# SCH_23GXSTM32F103Ext_2023-10-17.net
KiCad netlist of a schematic drawn in EasyEDA
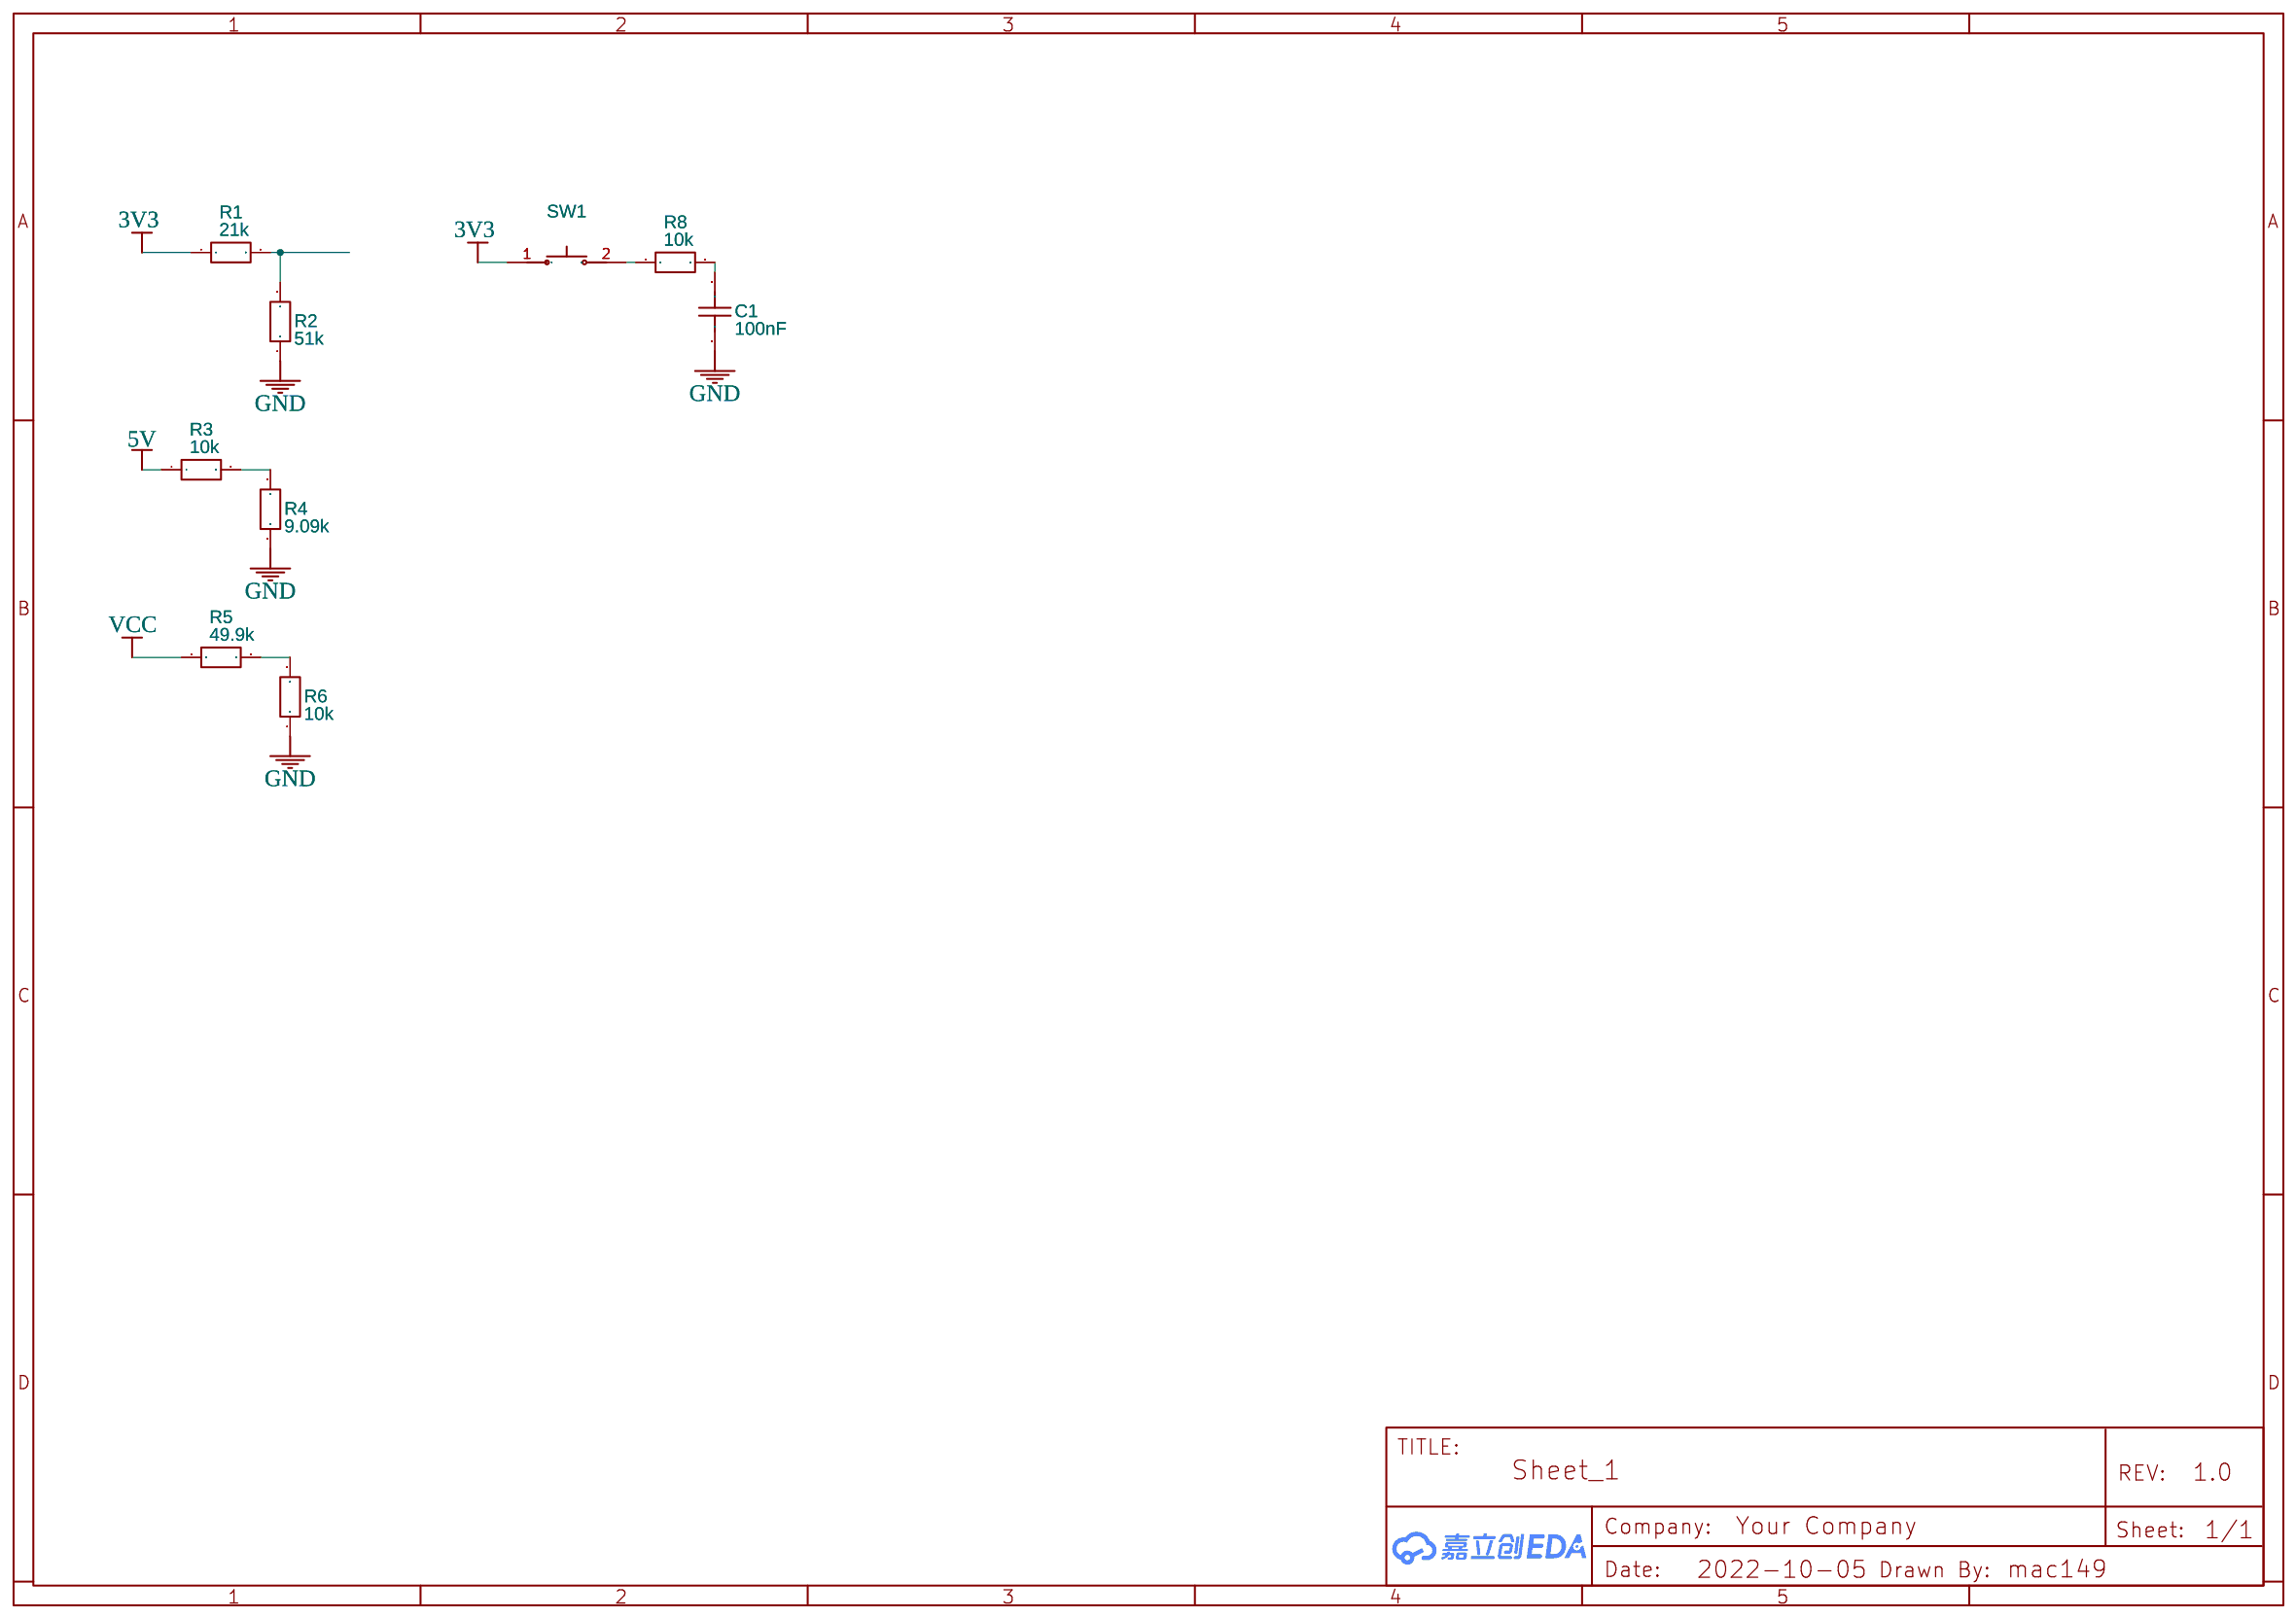
[diagram p0: Sheet_1]
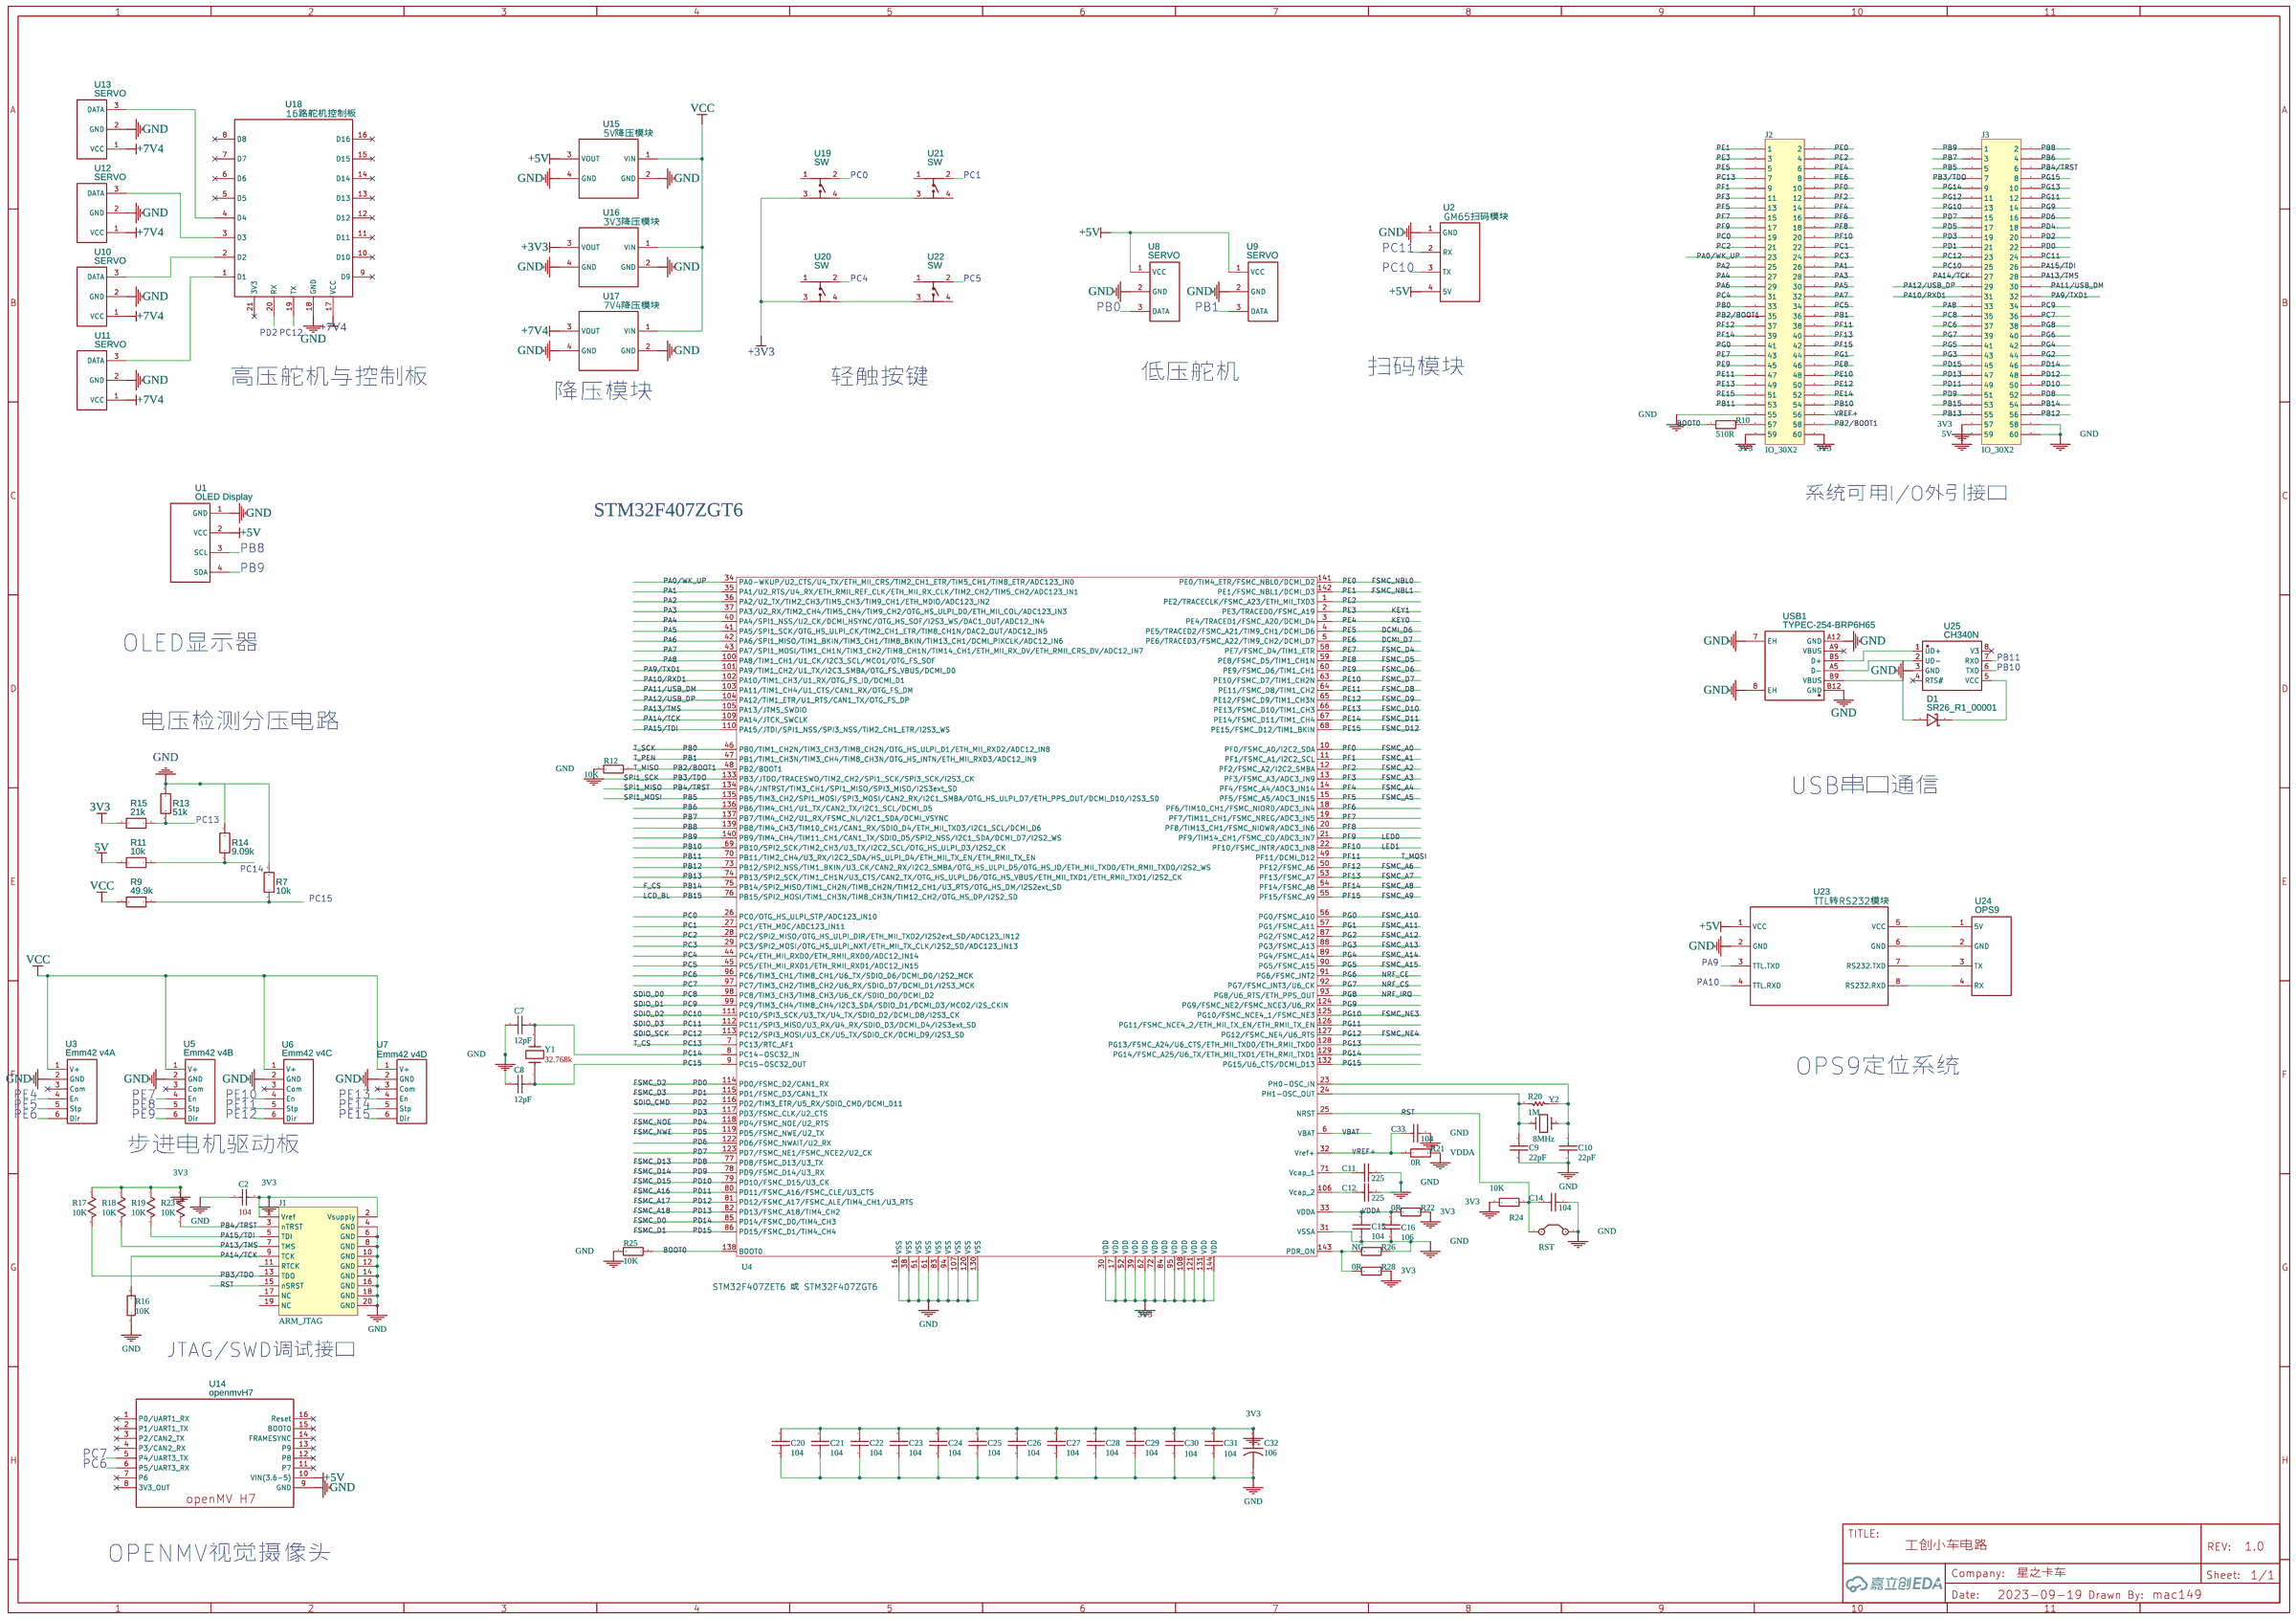
[diagram p1: Copy of STM32_F407.SchDoc]

(export (version "E")
  (design (tool "Eeschema 10.0.6"))
  (components
    (comp (ref "C1") (value "100nF") (libsource (lib "") (part "C_0603_US")))
    (comp (ref "R1") (value "21k") (libsource (lib "") (part "R_0603_EU_1")))
    (comp (ref "R2") (value "51k") (libsource (lib "") (part "R_0805_EU")))
    (comp (ref "R3") (value "10k") (libsource (lib "") (part "R_0805_EU_1")))
    (comp (ref "R4") (value "9.09k") (libsource (lib "") (part "R_0603_EU")))
    (comp (ref "R5") (value "49.9k") (libsource (lib "") (part "R_0805_EU_1")))
    (comp (ref "R6") (value "10k") (libsource (lib "") (part "R_0805_EU")))
    (comp (ref "R8") (value "10k") (libsource (lib "") (part "R_0603_EU_1")))
    (comp (ref "SW1")
      (value "TS3625A")
      (fields (field (name "Manufacturer") "SHOU HAN(首韩)"))
      (libsource (lib "") (part "TS3625A"))
    )
    (comp (ref "C2") (value "NO") (libsource (lib "") (part "Unknown_240_-435")))
    (comp (ref "C7") (value "12pF") (libsource (lib "") (part "Unknown_525_-600")))
    (comp (ref "C8") (value "12pF") (libsource (lib "") (part "Unknown_525_-540")))
    (comp (ref "C9") (value "22pF") (libsource (lib "") (part "Unknown_1540_-475")))
    (comp (ref "C10") (value "22pF") (libsource (lib "") (part "Unknown_1590_-475")))
    (comp (ref "C11") (value "225") (libsource (lib "") (part "Unknown_1385_-450")))
    (comp (ref "C12") (value "225") (libsource (lib "") (part "Unknown_1385_-430")))
    (comp (ref "C14") (value "104") (libsource (lib "") (part "Unknown_1575_-420")))
    (comp (ref "C15") (value "104") (libsource (lib "") (part "Unknown_1380_-395")))
    (comp (ref "C16") (value "106") (libsource (lib "") (part "Unknown_1410_-395")))
    (comp (ref "C20") (value "104") (libsource (lib "") (part "Unknown_790_-175")))
    (comp (ref "C21") (value "104") (libsource (lib "") (part "Unknown_830_-175")))
    (comp (ref "C22") (value "104") (libsource (lib "") (part "Unknown_870_-175")))
    (comp (ref "C23") (value "104") (libsource (lib "") (part "Unknown_910_-175")))
    (comp (ref "C24") (value "104") (libsource (lib "") (part "Unknown_950_-175")))
    (comp (ref "C25") (value "104") (libsource (lib "") (part "Unknown_990_-175")))
    (comp (ref "C26") (value "104") (libsource (lib "") (part "Unknown_1030_-175")))
    (comp (ref "C27") (value "104") (libsource (lib "") (part "Unknown_1070_-175")))
    (comp (ref "C28") (value "104") (libsource (lib "") (part "Unknown_1110_-175")))
    (comp (ref "C29") (value "104") (libsource (lib "") (part "Unknown_1150_-175")))
    (comp (ref "C30") (value "104") (libsource (lib "") (part "Unknown_1190_-175")))
    (comp (ref "C31") (value "104") (libsource (lib "") (part "Unknown_1230_-175")))
    (comp (ref "C32") (value "106") (libsource (lib "") (part "Unknown_1260_-180")))
    (comp (ref "C33") (value "104") (libsource (lib "") (part "Unknown_1435_-490")))
    (comp (ref "D1")
      (value "SR26_R1_00001")
      (fields (field (name "Manufacturer") "PANJIT(强茂)"))
      (libsource (lib "") (part "SR26_R1_00001"))
    )
    (comp (ref "J1") (value "ARM_JTAG") (libsource (lib "") (part "Unknown_280_-415")))
    (comp (ref "J2") (value "IO_30X2") (libsource (lib "") (part "Unknown_1790_-1500")))
    (comp (ref "J3") (value "IO_30X2") (libsource (lib "") (part "Unknown_2010_-1500")))
    (comp (ref "R7") (value "10k") (libsource (lib "") (part "R_0805_EU_1")))
    (comp (ref "R9") (value "49.9k") (libsource (lib "") (part "R_0805_EU")))
    (comp (ref "R10") (value "510R") (libsource (lib "") (part "Unknown_1760_-1200")))
    (comp (ref "R11") (value "10k") (libsource (lib "") (part "R_0805_EU")))
    (comp (ref "R12") (value "10K") (libsource (lib "") (part "Unknown_630_-850")))
    (comp (ref "R13") (value "51k") (libsource (lib "") (part "R_0805_EU_1")))
    (comp (ref "R14") (value "9.09k") (libsource (lib "") (part "R_0603_EU_1")))
    (comp (ref "R15") (value "21k") (libsource (lib "") (part "R_0603_EU")))
    (comp (ref "R16") (value "10K") (libsource (lib "") (part "Unknown_120_-305")))
    (comp (ref "R17") (value "10K") (libsource (lib "") (part "Unknown_90_-415")))
    (comp (ref "R18") (value "10K") (libsource (lib "") (part "Unknown_120_-415")))
    (comp (ref "R19") (value "10K") (libsource (lib "") (part "Unknown_150_-415")))
    (comp (ref "R20") (value "1M") (libsource (lib "") (part "Unknown_1570_-530")))
    (comp (ref "R21") (value "0R") (libsource (lib "") (part "Unknown_1430_-480")))
    (comp (ref "R22") (value "0R") (libsource (lib "") (part "Unknown_1420_-420")))
    (comp (ref "R23") (value "10K") (libsource (lib "") (part "Unknown_180_-415")))
    (comp (ref "R24") (value "10K") (libsource (lib "") (part "Unknown_1540_-410")))
    (comp (ref "R25") (value "10K") (libsource (lib "") (part "Unknown_650_-380")))
    (comp (ref "R26") (value "NC") (libsource (lib "") (part "Unknown_1380_-380")))
    (comp (ref "R28") (value "0R") (libsource (lib "") (part "Unknown_1380_-360")))
    (comp (ref "RST") (value "Key") (libsource (lib "") (part "Unknown_1560_-400")))
    (comp (ref "U1") (value "OLED Display") (libsource (lib "") (part "OLED Display")))
    (comp (ref "U2") (value "GM65扫码模块") (libsource (lib "") (part "GM65")))
    (comp (ref "U3") (value "Emm42 v4A") (libsource (lib "") (part "Emm42 v4")))
    (comp (ref "U4") (value "STM32F407ZET6 或 STM32F407ZGT6") (libsource (lib "") (part "Unknown_730_-1050")))
    (comp (ref "U5") (value "Emm42 v4B") (libsource (lib "") (part "Emm42 v4")))
    (comp (ref "U6") (value "Emm42 v4C") (libsource (lib "") (part "Emm42 v4")))
    (comp (ref "U7") (value "Emm42 v4D") (libsource (lib "") (part "Emm42 v4")))
    (comp (ref "U8") (value "SERVO") (libsource (lib "") (part "SERVO_1")))
    (comp (ref "U9") (value "SERVO") (libsource (lib "") (part "SERVO_1")))
    (comp (ref "U10") (value "SERVO") (libsource (lib "") (part "SERVO")))
    (comp (ref "U11") (value "SERVO") (libsource (lib "") (part "SERVO")))
    (comp (ref "U12") (value "SERVO") (libsource (lib "") (part "SERVO")))
    (comp (ref "U13") (value "SERVO") (libsource (lib "") (part "SERVO")))
    (comp (ref "U14") (value "openmvH7") (libsource (lib "") (part "openmvH7")))
    (comp (ref "U15") (value "5V降压模块") (libsource (lib "") (part "降压模块")))
    (comp (ref "U16") (value "3V3降压模块") (libsource (lib "") (part "降压模块")))
    (comp (ref "U17") (value "7V4降压模块") (libsource (lib "") (part "降压模块")))
    (comp (ref "U18") (value "16路舵机控制板") (libsource (lib "") (part "16路舵机控制板")))
    (comp (ref "U19")
      (value "SW")
      (fields
        (field (name "Manufacturer Part") "TD-1806SR-5.5H-250")
        (field (name "Manufacturer") "DEALON(德艺隆)")
      )
      (libsource (lib "") (part "TD-1806SR-5.5H-250"))
    )
    (comp (ref "U20")
      (value "SW")
      (fields
        (field (name "Manufacturer Part") "TD-1806SR-5.5H-250")
        (field (name "Manufacturer") "DEALON(德艺隆)")
      )
      (libsource (lib "") (part "TD-1806SR-5.5H-250"))
    )
    (comp (ref "U21")
      (value "SW")
      (fields
        (field (name "Manufacturer Part") "TD-1806SR-5.5H-250")
        (field (name "Manufacturer") "DEALON(德艺隆)")
      )
      (libsource (lib "") (part "TD-1806SR-5.5H-250"))
    )
    (comp (ref "U22")
      (value "SW")
      (fields
        (field (name "Manufacturer Part") "TD-1806SR-5.5H-250")
        (field (name "Manufacturer") "DEALON(德艺隆)")
      )
      (libsource (lib "") (part "TD-1806SR-5.5H-250"))
    )
    (comp (ref "U23") (value "TTL转RS232模块") (libsource (lib "") (part "TTL转RS232模块")))
    (comp (ref "U24") (value "OPS9") (libsource (lib "") (part "GM65_1")))
    (comp (ref "U25")
      (value "CH340N")
      (fields (field (name "Manufacturer") "WCH(南京沁恒)"))
      (libsource (lib "") (part "CH340N"))
    )
    (comp (ref "USB1")
      (value "TYPEC-254-BRP6H65")
      (fields (field (name "Manufacturer") "XUNPU(讯普)"))
      (libsource (lib "") (part "TYPEC-254-BRP6H65"))
    )
    (comp (ref "Y1") (value "8MHz") (libsource (lib "") (part "Unknown_550_-560")))
    (comp (ref "Y2") (value "8MHz") (libsource (lib "") (part "Unknown_1565_-500")))
  )
  (nets
    (net (code "1") (name "+3V3") (class "Default")
      (node (ref "U16") (pin "3") (pinfunction "VOUT_3") (pintype "unspecified"))
      (node (ref "U19") (pin "3") (pinfunction "C_3") (pintype "unspecified"))
      (node (ref "U20") (pin "3") (pinfunction "C_3") (pintype "unspecified"))
    )
    (net (code "2") (name "+5V") (class "Default")
      (node (ref "U1") (pin "2") (pinfunction "VCC_2") (pintype "unspecified"))
      (node (ref "U14") (pin "10") (pinfunction "VIN(3.6-5)_10") (pintype "unspecified"))
      (node (ref "U15") (pin "3") (pinfunction "VOUT_3") (pintype "unspecified"))
      (node (ref "U2") (pin "4") (pinfunction "5V_4") (pintype "unspecified"))
      (node (ref "U23") (pin "1") (pinfunction "VCC_1") (pintype "unspecified"))
      (node (ref "U8") (pin "1") (pinfunction "VCC_1") (pintype "unspecified"))
      (node (ref "U9") (pin "1") (pinfunction "VCC_1") (pintype "unspecified"))
    )
    (net (code "3") (name "+7V4") (class "Default")
      (node (ref "U10") (pin "1") (pinfunction "VCC_1") (pintype "unspecified"))
      (node (ref "U11") (pin "1") (pinfunction "VCC_1") (pintype "unspecified"))
      (node (ref "U12") (pin "1") (pinfunction "VCC_1") (pintype "unspecified"))
      (node (ref "U13") (pin "1") (pinfunction "VCC_1") (pintype "unspecified"))
      (node (ref "U17") (pin "3") (pinfunction "VOUT_3") (pintype "unspecified"))
      (node (ref "U18") (pin "17") (pinfunction "VCC_17") (pintype "unspecified"))
    )
    (net (code "4") (name "3V3") (class "Default")
      (node (ref "C2") (pin "2") (pinfunction "2_2") (pintype "unspecified"))
      (node (ref "C20") (pin "1") (pinfunction "1_1") (pintype "unspecified"))
      (node (ref "C21") (pin "1") (pinfunction "1_1") (pintype "unspecified"))
      (node (ref "C22") (pin "1") (pinfunction "1_1") (pintype "unspecified"))
      (node (ref "C23") (pin "1") (pinfunction "1_1") (pintype "unspecified"))
      (node (ref "C24") (pin "1") (pinfunction "1_1") (pintype "unspecified"))
      (node (ref "C25") (pin "1") (pinfunction "1_1") (pintype "unspecified"))
      (node (ref "C26") (pin "1") (pinfunction "1_1") (pintype "unspecified"))
      (node (ref "C27") (pin "1") (pinfunction "1_1") (pintype "unspecified"))
      (node (ref "C28") (pin "1") (pinfunction "1_1") (pintype "unspecified"))
      (node (ref "C29") (pin "1") (pinfunction "1_1") (pintype "unspecified"))
      (node (ref "C30") (pin "1") (pinfunction "1_1") (pintype "unspecified"))
      (node (ref "C31") (pin "1") (pinfunction "1_1") (pintype "unspecified"))
      (node (ref "C32") (pin "1") (pinfunction "1_1") (pintype "unspecified"))
      (node (ref "J1") (pin "1") (pinfunction "Vref_1") (pintype "unspecified"))
      (node (ref "J1") (pin "2") (pinfunction "Vsupply_2") (pintype "unspecified"))
      (node (ref "J2") (pin "59") (pinfunction "59_59") (pintype "unspecified"))
      (node (ref "J2") (pin "60") (pinfunction "60_60") (pintype "unspecified"))
      (node (ref "J3") (pin "57") (pinfunction "57_57") (pintype "unspecified"))
      (node (ref "R1") (pin "1") (pinfunction "1_1") (pintype "unspecified"))
      (node (ref "R15") (pin "1") (pinfunction "1_1") (pintype "unspecified"))
      (node (ref "R17") (pin "1") (pinfunction "1_1") (pintype "unspecified"))
      (node (ref "R18") (pin "1") (pinfunction "1_1") (pintype "unspecified"))
      (node (ref "R19") (pin "1") (pinfunction "1_1") (pintype "unspecified"))
      (node (ref "R22") (pin "2") (pinfunction "2_2") (pintype "unspecified"))
      (node (ref "R23") (pin "1") (pinfunction "1_1") (pintype "unspecified"))
      (node (ref "R24") (pin "2") (pinfunction "2_2") (pintype "unspecified"))
      (node (ref "R28") (pin "2") (pinfunction "2_2") (pintype "unspecified"))
      (node (ref "SW1") (pin "1") (pinfunction "1_1") (pintype "unspecified"))
      (node (ref "U4") (pin "108") (pinfunction "VDD_108") (pintype "unspecified"))
      (node (ref "U4") (pin "121") (pinfunction "VDD_121") (pintype "unspecified"))
      (node (ref "U4") (pin "131") (pinfunction "VDD_131") (pintype "unspecified"))
      (node (ref "U4") (pin "144") (pinfunction "VDD_144") (pintype "unspecified"))
      (node (ref "U4") (pin "17") (pinfunction "VDD_17") (pintype "unspecified"))
      (node (ref "U4") (pin "30") (pinfunction "VDD_30") (pintype "unspecified"))
      (node (ref "U4") (pin "39") (pinfunction "VDD_39") (pintype "unspecified"))
      (node (ref "U4") (pin "52") (pinfunction "VDD_52") (pintype "unspecified"))
      (node (ref "U4") (pin "62") (pinfunction "VDD_62") (pintype "unspecified"))
      (node (ref "U4") (pin "72") (pinfunction "VDD_72") (pintype "unspecified"))
      (node (ref "U4") (pin "84") (pinfunction "VDD_84") (pintype "unspecified"))
      (node (ref "U4") (pin "95") (pinfunction "VDD_95") (pintype "unspecified"))
    )
    (net (code "5") (name "5V") (class "Default")
      (node (ref "J3") (pin "59") (pinfunction "59_59") (pintype "unspecified"))
      (node (ref "R11") (pin "1") (pinfunction "1_1") (pintype "unspecified"))
      (node (ref "R3") (pin "1") (pinfunction "1_1") (pintype "unspecified"))
    )
    (net (code "6") (name "BOOT0") (class "Default")
      (node (ref "R10") (pin "2") (pinfunction "2_2") (pintype "unspecified"))
      (node (ref "R25") (pin "1") (pinfunction "1_1") (pintype "unspecified"))
      (node (ref "U4") (pin "138") (pinfunction "BOOT0_138") (pintype "unspecified"))
    )
    (net (code "7") (name "DCMI_D6") (class "Default")
      (node (ref "J2") (pin "5") (pinfunction "5_5") (pintype "unspecified"))
      (node (ref "U4") (pin "4") (pinfunction "PE5/TRACED2/FSMC_A21/TIM9_CH1/DCMI_D6_4") (pintype "unspecified"))
    )
    (net (code "8") (name "DCMI_D7") (class "Default")
      (node (ref "J2") (pin "8") (pinfunction "8_8") (pintype "unspecified"))
      (node (ref "U4") (pin "5") (pinfunction "PE6/TRACED3/FSMC_A22/TIM9_CH2/DCMI_D7_5") (pintype "unspecified"))
    )
    (net (code "9") (name "FSMC_A0") (class "Default")
      (node (ref "J2") (pin "10") (pinfunction "10_10") (pintype "unspecified"))
      (node (ref "U4") (pin "10") (pinfunction "PF0/FSMC_A0/I2C2_SDA_10") (pintype "unspecified"))
    )
    (net (code "10") (name "FSMC_A1") (class "Default")
      (node (ref "J2") (pin "9") (pinfunction "9_9") (pintype "unspecified"))
      (node (ref "U4") (pin "11") (pinfunction "PF1/FSMC_A1/I2C2_SCL_11") (pintype "unspecified"))
    )
    (net (code "11") (name "FSMC_A2") (class "Default")
      (node (ref "J2") (pin "12") (pinfunction "12_12") (pintype "unspecified"))
      (node (ref "U4") (pin "12") (pinfunction "PF2/FSMC_A2/I2C2_SMBA_12") (pintype "unspecified"))
    )
    (net (code "12") (name "FSMC_A3") (class "Default")
      (node (ref "J2") (pin "11") (pinfunction "11_11") (pintype "unspecified"))
      (node (ref "U4") (pin "13") (pinfunction "PF3/FSMC_A3/ADC3_IN9_13") (pintype "unspecified"))
    )
    (net (code "13") (name "FSMC_A4") (class "Default")
      (node (ref "J2") (pin "14") (pinfunction "14_14") (pintype "unspecified"))
      (node (ref "U4") (pin "14") (pinfunction "PF4/FSMC_A4/ADC3_IN14_14") (pintype "unspecified"))
    )
    (net (code "14") (name "FSMC_A5") (class "Default")
      (node (ref "J2") (pin "13") (pinfunction "13_13") (pintype "unspecified"))
      (node (ref "U4") (pin "15") (pinfunction "PF5/FSMC_A5/ADC3_IN15_15") (pintype "unspecified"))
    )
    (net (code "15") (name "FSMC_A6") (class "Default")
      (node (ref "J2") (pin "37") (pinfunction "37_37") (pintype "unspecified"))
      (node (ref "U4") (pin "50") (pinfunction "PF12/FSMC_A6_50") (pintype "unspecified"))
    )
    (net (code "16") (name "FSMC_A7") (class "Default")
      (node (ref "J2") (pin "40") (pinfunction "40_40") (pintype "unspecified"))
      (node (ref "U4") (pin "53") (pinfunction "PF13/FSMC_A7_53") (pintype "unspecified"))
    )
    (net (code "17") (name "FSMC_A8") (class "Default")
      (node (ref "J2") (pin "39") (pinfunction "39_39") (pintype "unspecified"))
      (node (ref "U4") (pin "54") (pinfunction "PF14/FSMC_A8_54") (pintype "unspecified"))
    )
    (net (code "18") (name "FSMC_A9") (class "Default")
      (node (ref "J2") (pin "42") (pinfunction "42_42") (pintype "unspecified"))
      (node (ref "U4") (pin "55") (pinfunction "PF15/FSMC_A9_55") (pintype "unspecified"))
    )
    (net (code "19") (name "FSMC_A10") (class "Default")
      (node (ref "J2") (pin "41") (pinfunction "41_41") (pintype "unspecified"))
      (node (ref "U4") (pin "56") (pinfunction "PG0/FSMC_A10_56") (pintype "unspecified"))
    )
    (net (code "20") (name "FSMC_A11") (class "Default")
      (node (ref "J2") (pin "44") (pinfunction "44_44") (pintype "unspecified"))
      (node (ref "U4") (pin "57") (pinfunction "PG1/FSMC_A11_57") (pintype "unspecified"))
    )
    (net (code "21") (name "FSMC_A12") (class "Default")
      (node (ref "J3") (pin "44") (pinfunction "44_44") (pintype "unspecified"))
      (node (ref "U4") (pin "87") (pinfunction "PG2/FSMC_A12_87") (pintype "unspecified"))
    )
    (net (code "22") (name "FSMC_A13") (class "Default")
      (node (ref "J3") (pin "43") (pinfunction "43_43") (pintype "unspecified"))
      (node (ref "U4") (pin "88") (pinfunction "PG3/FSMC_A13_88") (pintype "unspecified"))
    )
    (net (code "23") (name "FSMC_A14") (class "Default")
      (node (ref "J3") (pin "42") (pinfunction "42_42") (pintype "unspecified"))
      (node (ref "U4") (pin "89") (pinfunction "PG4/FSMC_A14_89") (pintype "unspecified"))
    )
    (net (code "24") (name "FSMC_A15") (class "Default")
      (node (ref "J3") (pin "41") (pinfunction "41_41") (pintype "unspecified"))
      (node (ref "U4") (pin "90") (pinfunction "PG5/FSMC_A15_90") (pintype "unspecified"))
    )
    (net (code "25") (name "FSMC_A16") (class "Default")
      (node (ref "J3") (pin "49") (pinfunction "49_49") (pintype "unspecified"))
      (node (ref "U4") (pin "80") (pinfunction "PD11/FSMC_A16/FSMC_CLE/U3_CTS_80") (pintype "unspecified"))
    )
    (net (code "26") (name "FSMC_A17") (class "Default")
      (node (ref "J3") (pin "48") (pinfunction "48_48") (pintype "unspecified"))
      (node (ref "U4") (pin "81") (pinfunction "PD12/FSMC_A17/FSMC_ALE/TIM4_CH1/U3_RTS_81") (pintype "unspecified"))
    )
    (net (code "27") (name "FSMC_A18") (class "Default")
      (node (ref "J3") (pin "47") (pinfunction "47_47") (pintype "unspecified"))
      (node (ref "U4") (pin "82") (pinfunction "PD13/FSMC_A18/TIM4_CH2_82") (pintype "unspecified"))
    )
    (net (code "28") (name "FSMC_D0") (class "Default")
      (node (ref "J3") (pin "46") (pinfunction "46_46") (pintype "unspecified"))
      (node (ref "U4") (pin "85") (pinfunction "PD14/FSMC_D0/TIM4_CH3_85") (pintype "unspecified"))
    )
    (net (code "29") (name "FSMC_D1") (class "Default")
      (node (ref "J3") (pin "45") (pinfunction "45_45") (pintype "unspecified"))
      (node (ref "U4") (pin "86") (pinfunction "PD15/FSMC_D1/TIM4_CH4_86") (pintype "unspecified"))
    )
    (net (code "30") (name "FSMC_D2") (class "Default")
      (node (ref "J3") (pin "22") (pinfunction "22_22") (pintype "unspecified"))
      (node (ref "U4") (pin "114") (pinfunction "PD0/FSMC_D2/CAN1_RX_114") (pintype "unspecified"))
    )
    (net (code "31") (name "FSMC_D3") (class "Default")
      (node (ref "J3") (pin "21") (pinfunction "21_21") (pintype "unspecified"))
      (node (ref "U4") (pin "115") (pinfunction "PD1/FSMC_D3/CAN1_TX_115") (pintype "unspecified"))
    )
    (net (code "32") (name "FSMC_D4") (class "Default")
      (node (ref "J2") (pin "43") (pinfunction "43_43") (pintype "unspecified"))
      (node (ref "U4") (pin "58") (pinfunction "PE7/FSMC_D4/TIM1_ETR_58") (pintype "unspecified"))
    )
    (net (code "33") (name "FSMC_D5") (class "Default")
      (node (ref "J2") (pin "46") (pinfunction "46_46") (pintype "unspecified"))
      (node (ref "U4") (pin "59") (pinfunction "PE8/FSMC_D5/TIM1_CH1N_59") (pintype "unspecified"))
    )
    (net (code "34") (name "FSMC_D6") (class "Default")
      (node (ref "J2") (pin "45") (pinfunction "45_45") (pintype "unspecified"))
      (node (ref "U4") (pin "60") (pinfunction "PE9/FSMC_D6/TIM1_CH1_60") (pintype "unspecified"))
    )
    (net (code "35") (name "FSMC_D7") (class "Default")
      (node (ref "J2") (pin "48") (pinfunction "48_48") (pintype "unspecified"))
      (node (ref "U4") (pin "63") (pinfunction "PE10/FSMC_D7/TIM1_CH2N_63") (pintype "unspecified"))
    )
    (net (code "36") (name "FSMC_D8") (class "Default")
      (node (ref "J2") (pin "47") (pinfunction "47_47") (pintype "unspecified"))
      (node (ref "U4") (pin "64") (pinfunction "PE11/FSMC_D8/TIM1_CH2_64") (pintype "unspecified"))
    )
    (net (code "37") (name "FSMC_D9") (class "Default")
      (node (ref "J2") (pin "50") (pinfunction "50_50") (pintype "unspecified"))
      (node (ref "U4") (pin "65") (pinfunction "PE12/FSMC_D9/TIM1_CH3N_65") (pintype "unspecified"))
    )
    (net (code "38") (name "FSMC_D10") (class "Default")
      (node (ref "J2") (pin "49") (pinfunction "49_49") (pintype "unspecified"))
      (node (ref "U4") (pin "66") (pinfunction "PE13/FSMC_D10/TIM1_CH3_66") (pintype "unspecified"))
    )
    (net (code "39") (name "FSMC_D11") (class "Default")
      (node (ref "J2") (pin "52") (pinfunction "52_52") (pintype "unspecified"))
      (node (ref "U4") (pin "67") (pinfunction "PE14/FSMC_D11/TIM1_CH4_67") (pintype "unspecified"))
    )
    (net (code "40") (name "FSMC_D12") (class "Default")
      (node (ref "J2") (pin "51") (pinfunction "51_51") (pintype "unspecified"))
      (node (ref "U4") (pin "68") (pinfunction "PE15/FSMC_D12/TIM1_BKIN_68") (pintype "unspecified"))
    )
    (net (code "41") (name "FSMC_D13") (class "Default")
      (node (ref "J3") (pin "52") (pinfunction "52_52") (pintype "unspecified"))
      (node (ref "U4") (pin "77") (pinfunction "PD8/FSMC_D13/U3_TX_77") (pintype "unspecified"))
    )
    (net (code "42") (name "FSMC_D14") (class "Default")
      (node (ref "J3") (pin "51") (pinfunction "51_51") (pintype "unspecified"))
      (node (ref "U4") (pin "78") (pinfunction "PD9/FSMC_D14/U3_RX_78") (pintype "unspecified"))
    )
    (net (code "43") (name "FSMC_D15") (class "Default")
      (node (ref "J3") (pin "50") (pinfunction "50_50") (pintype "unspecified"))
      (node (ref "U4") (pin "79") (pinfunction "PD10/FSMC_D15/U3_CK_79") (pintype "unspecified"))
    )
    (net (code "44") (name "FSMC_NBL0") (class "Default")
      (node (ref "J2") (pin "2") (pinfunction "2_2") (pintype "unspecified"))
      (node (ref "U4") (pin "141") (pinfunction "PE0/TIM4_ETR/FSMC_NBL0/DCMI_D2_141") (pintype "unspecified"))
    )
    (net (code "45") (name "FSMC_NBL1") (class "Default")
      (node (ref "J2") (pin "1") (pinfunction "1_1") (pintype "unspecified"))
      (node (ref "U4") (pin "142") (pinfunction "PE1/FSMC_NBL1/DCMI_D3_142") (pintype "unspecified"))
    )
    (net (code "46") (name "FSMC_NE3") (class "Default")
      (node (ref "J3") (pin "13") (pinfunction "13_13") (pintype "unspecified"))
      (node (ref "U4") (pin "125") (pinfunction "PG10/FSMC_NCE4_1/FSMC_NE3_125") (pintype "unspecified"))
    )
    (net (code "47") (name "FSMC_NE4") (class "Default")
      (node (ref "J3") (pin "11") (pinfunction "11_11") (pintype "unspecified"))
      (node (ref "U4") (pin "127") (pinfunction "PG12/FSMC_NE4/U6_RTS_127") (pintype "unspecified"))
    )
    (net (code "48") (name "FSMC_NOE") (class "Default")
      (node (ref "J3") (pin "18") (pinfunction "18_18") (pintype "unspecified"))
      (node (ref "U4") (pin "118") (pinfunction "PD4/FSMC_NOE/U2_RTS_118") (pintype "unspecified"))
    )
    (net (code "49") (name "FSMC_NWE") (class "Default")
      (node (ref "J3") (pin "17") (pinfunction "17_17") (pintype "unspecified"))
      (node (ref "U4") (pin "119") (pinfunction "PD5/FSMC_NWE/U2_TX_119") (pintype "unspecified"))
    )
    (net (code "50") (name "F_CS") (class "Default")
      (node (ref "J3") (pin "54") (pinfunction "54_54") (pintype "unspecified"))
      (node (ref "U4") (pin "75") (pinfunction "PB14/SPI2_MISO/TIM1_CH2N/TIM8_CH2N/TIM12_CH1/U3_RTS/OTG_HS_DM/I2S2ext_SD_75") (pintype "unspecified"))
    )
    (net (code "51") (name "GND") (class "Default")
      (node (ref "C1") (pin "1") (pinfunction "1_1") (pintype "unspecified"))
      (node (ref "C10") (pin "2") (pinfunction "2_2") (pintype "unspecified"))
      (node (ref "C11") (pin "2") (pinfunction "2_2") (pintype "unspecified"))
      (node (ref "C12") (pin "2") (pinfunction "2_2") (pintype "unspecified"))
      (node (ref "C14") (pin "1") (pinfunction "1_1") (pintype "unspecified"))
      (node (ref "C15") (pin "1") (pinfunction "1_1") (pintype "unspecified"))
      (node (ref "C16") (pin "1") (pinfunction "1_1") (pintype "unspecified"))
      (node (ref "C2") (pin "1") (pinfunction "1_1") (pintype "unspecified"))
      (node (ref "C20") (pin "2") (pinfunction "2_2") (pintype "unspecified"))
      (node (ref "C21") (pin "2") (pinfunction "2_2") (pintype "unspecified"))
      (node (ref "C22") (pin "2") (pinfunction "2_2") (pintype "unspecified"))
      (node (ref "C23") (pin "2") (pinfunction "2_2") (pintype "unspecified"))
      (node (ref "C24") (pin "2") (pinfunction "2_2") (pintype "unspecified"))
      (node (ref "C25") (pin "2") (pinfunction "2_2") (pintype "unspecified"))
      (node (ref "C26") (pin "2") (pinfunction "2_2") (pintype "unspecified"))
      (node (ref "C27") (pin "2") (pinfunction "2_2") (pintype "unspecified"))
      (node (ref "C28") (pin "2") (pinfunction "2_2") (pintype "unspecified"))
      (node (ref "C29") (pin "2") (pinfunction "2_2") (pintype "unspecified"))
      (node (ref "C30") (pin "2") (pinfunction "2_2") (pintype "unspecified"))
      (node (ref "C31") (pin "2") (pinfunction "2_2") (pintype "unspecified"))
      (node (ref "C32") (pin "2") (pinfunction "2_2") (pintype "unspecified"))
      (node (ref "C33") (pin "2") (pinfunction "2_2") (pintype "unspecified"))
      (node (ref "C7") (pin "1") (pinfunction "1_1") (pintype "unspecified"))
      (node (ref "C8") (pin "1") (pinfunction "1_1") (pintype "unspecified"))
      (node (ref "C9") (pin "2") (pinfunction "2_2") (pintype "unspecified"))
      (node (ref "J1") (pin "10") (pinfunction "GND_10") (pintype "unspecified"))
      (node (ref "J1") (pin "12") (pinfunction "GND_12") (pintype "unspecified"))
      (node (ref "J1") (pin "14") (pinfunction "GND_14") (pintype "unspecified"))
      (node (ref "J1") (pin "16") (pinfunction "GND_16") (pintype "unspecified"))
      (node (ref "J1") (pin "18") (pinfunction "GND_18") (pintype "unspecified"))
      (node (ref "J1") (pin "20") (pinfunction "GND_20") (pintype "unspecified"))
      (node (ref "J1") (pin "4") (pinfunction "GND_4") (pintype "unspecified"))
      (node (ref "J1") (pin "6") (pinfunction "GND_6") (pintype "unspecified"))
      (node (ref "J1") (pin "8") (pinfunction "GND_8") (pintype "unspecified"))
      (node (ref "J2") (pin "55") (pinfunction "55_55") (pintype "unspecified"))
      (node (ref "J3") (pin "58") (pinfunction "58_58") (pintype "unspecified"))
      (node (ref "J3") (pin "60") (pinfunction "60_60") (pintype "unspecified"))
      (node (ref "R12") (pin "2") (pinfunction "2_2") (pintype "unspecified"))
      (node (ref "R13") (pin "2") (pinfunction "2_2") (pintype "unspecified"))
      (node (ref "R14") (pin "2") (pinfunction "2_2") (pintype "unspecified"))
      (node (ref "R16") (pin "1") (pinfunction "1_1") (pintype "unspecified"))
      (node (ref "R2") (pin "1") (pinfunction "1_1") (pintype "unspecified"))
      (node (ref "R25") (pin "2") (pinfunction "2_2") (pintype "unspecified"))
      (node (ref "R26") (pin "2") (pinfunction "2_2") (pintype "unspecified"))
      (node (ref "R4") (pin "1") (pinfunction "1_1") (pintype "unspecified"))
      (node (ref "R6") (pin "1") (pinfunction "1_1") (pintype "unspecified"))
      (node (ref "R7") (pin "2") (pinfunction "2_2") (pintype "unspecified"))
      (node (ref "RST") (pin "2") (pinfunction "C2_2") (pintype "unspecified"))
      (node (ref "U1") (pin "1") (pinfunction "GND_1") (pintype "unspecified"))
      (node (ref "U10") (pin "2") (pinfunction "GND_2") (pintype "unspecified"))
      (node (ref "U11") (pin "2") (pinfunction "GND_2") (pintype "unspecified"))
      (node (ref "U12") (pin "2") (pinfunction "GND_2") (pintype "unspecified"))
      (node (ref "U13") (pin "2") (pinfunction "GND_2") (pintype "unspecified"))
      (node (ref "U14") (pin "9") (pinfunction "GND_9") (pintype "unspecified"))
      (node (ref "U15") (pin "2") (pinfunction "GND_2") (pintype "unspecified"))
      (node (ref "U15") (pin "4") (pinfunction "GND_4") (pintype "unspecified"))
      (node (ref "U16") (pin "2") (pinfunction "GND_2") (pintype "unspecified"))
      (node (ref "U16") (pin "4") (pinfunction "GND_4") (pintype "unspecified"))
      (node (ref "U17") (pin "2") (pinfunction "GND_2") (pintype "unspecified"))
      (node (ref "U17") (pin "4") (pinfunction "GND_4") (pintype "unspecified"))
      (node (ref "U18") (pin "18") (pinfunction "GND_18") (pintype "unspecified"))
      (node (ref "U2") (pin "1") (pinfunction "GND_1") (pintype "unspecified"))
      (node (ref "U23") (pin "2") (pinfunction "GND_2") (pintype "unspecified"))
      (node (ref "U25") (pin "3") (pinfunction "GND_3") (pintype "unspecified"))
      (node (ref "U3") (pin "2") (pinfunction "GND_2") (pintype "unspecified"))
      (node (ref "U4") (pin "107") (pinfunction "VSS_107") (pintype "unspecified"))
      (node (ref "U4") (pin "120") (pinfunction "VSS_120") (pintype "unspecified"))
      (node (ref "U4") (pin "130") (pinfunction "VSS_130") (pintype "unspecified"))
      (node (ref "U4") (pin "16") (pinfunction "VSS_16") (pintype "unspecified"))
      (node (ref "U4") (pin "31") (pinfunction "VSSA_31") (pintype "unspecified"))
      (node (ref "U4") (pin "38") (pinfunction "VSS_38") (pintype "unspecified"))
      (node (ref "U4") (pin "51") (pinfunction "VSS_51") (pintype "unspecified"))
      (node (ref "U4") (pin "61") (pinfunction "VSS_61") (pintype "unspecified"))
      (node (ref "U4") (pin "83") (pinfunction "VSS_83") (pintype "unspecified"))
      (node (ref "U4") (pin "94") (pinfunction "VSS_94") (pintype "unspecified"))
      (node (ref "U5") (pin "2") (pinfunction "GND_2") (pintype "unspecified"))
      (node (ref "U6") (pin "2") (pinfunction "GND_2") (pintype "unspecified"))
      (node (ref "U7") (pin "2") (pinfunction "GND_2") (pintype "unspecified"))
      (node (ref "U8") (pin "2") (pinfunction "GND_2") (pintype "unspecified"))
      (node (ref "U9") (pin "2") (pinfunction "GND_2") (pintype "unspecified"))
      (node (ref "USB1") (pin "7") (pinfunction "EH_7") (pintype "unspecified"))
      (node (ref "USB1") (pin "8") (pinfunction "EH_8") (pintype "unspecified"))
      (node (ref "USB1") (pin "A12") (pinfunction "GND_A12") (pintype "unspecified"))
      (node (ref "USB1") (pin "B12") (pinfunction "GND_B12") (pintype "unspecified"))
    )
    (net (code "52") (name "KEY0") (class "Default")
      (node (ref "J2") (pin "6") (pinfunction "6_6") (pintype "unspecified"))
      (node (ref "U4") (pin "3") (pinfunction "PE4/TRACED1/FSMC_A20/DCMI_D4_3") (pintype "unspecified"))
    )
    (net (code "53") (name "KEY1") (class "Default")
      (node (ref "J2") (pin "3") (pinfunction "3_3") (pintype "unspecified"))
      (node (ref "U4") (pin "2") (pinfunction "PE3/TRACED0/FSMC_A19_2") (pintype "unspecified"))
    )
    (net (code "54") (name "LCD_BL") (class "Default")
      (node (ref "J3") (pin "53") (pinfunction "53_53") (pintype "unspecified"))
      (node (ref "U4") (pin "76") (pinfunction "PB15/SPI2_MOSI/TIM1_CH3N/TIM8_CH3N/TIM12_CH2/OTG_HS_DP/I2S2_SD_76") (pintype "unspecified"))
    )
    (net (code "55") (name "LED0") (class "Default")
      (node (ref "J2") (pin "17") (pinfunction "17_17") (pintype "unspecified"))
      (node (ref "U4") (pin "21") (pinfunction "PF9/TIM14_CH1/FSMC_CD/ADC3_IN7_21") (pintype "unspecified"))
    )
    (net (code "56") (name "LED1") (class "Default")
      (node (ref "J2") (pin "20") (pinfunction "20_20") (pintype "unspecified"))
      (node (ref "U4") (pin "22") (pinfunction "PF10/FSMC_INTR/ADC3_IN8_22") (pintype "unspecified"))
    )
    (net (code "57") (name "NRF_CE") (class "Default")
      (node (ref "J3") (pin "40") (pinfunction "40_40") (pintype "unspecified"))
      (node (ref "U4") (pin "91") (pinfunction "PG6/FSMC_INT2_91") (pintype "unspecified"))
    )
    (net (code "58") (name "NRF_CS") (class "Default")
      (node (ref "J3") (pin "39") (pinfunction "39_39") (pintype "unspecified"))
      (node (ref "U4") (pin "92") (pinfunction "PG7/FSMC_INT3/U6_CK_92") (pintype "unspecified"))
    )
    (net (code "59") (name "NRF_IRQ") (class "Default")
      (node (ref "J3") (pin "38") (pinfunction "38_38") (pintype "unspecified"))
      (node (ref "U4") (pin "93") (pinfunction "PG8/U6_RTS/ETH_PPS_OUT_93") (pintype "unspecified"))
    )
    (net (code "60") (name "Net-(C1-Pad2)") (class "Default")
      (node (ref "C1") (pin "2") (pinfunction "2_2") (pintype "unspecified"))
      (node (ref "R8") (pin "2") (pinfunction "2_2") (pintype "unspecified"))
    )
    (net (code "61") (name "Net-(D1-Pad2)") (class "Default")
      (node (ref "D1") (pin "2") (pinfunction "2_2") (pintype "unspecified"))
      (node (ref "USB1") (pin "B9") (pinfunction "VBUS_B9") (pintype "unspecified"))
    )
    (net (code "62") (name "Net-(J2-Pad57)") (class "Default")
      (node (ref "J2") (pin "57") (pinfunction "57_57") (pintype "unspecified"))
      (node (ref "R10") (pin "1") (pinfunction "1_1") (pintype "unspecified"))
    )
    (net (code "63") (name "Net-(R1-Pad2)") (class "Default")
      (node (ref "R1") (pin "2") (pinfunction "2_2") (pintype "unspecified"))
      (node (ref "R2") (pin "2") (pinfunction "2_2") (pintype "unspecified"))
    )
    (net (code "64") (name "Net-(R3-Pad2)") (class "Default")
      (node (ref "R3") (pin "2") (pinfunction "2_2") (pintype "unspecified"))
      (node (ref "R4") (pin "2") (pinfunction "2_2") (pintype "unspecified"))
    )
    (net (code "65") (name "Net-(R5-Pad2)") (class "Default")
      (node (ref "R5") (pin "2") (pinfunction "2_2") (pintype "unspecified"))
      (node (ref "R6") (pin "2") (pinfunction "2_2") (pintype "unspecified"))
    )
    (net (code "66") (name "Net-(R7-Pad1)") (class "Default")
      (node (ref "R7") (pin "1") (pinfunction "1_1") (pintype "unspecified"))
      (node (ref "R9") (pin "2") (pinfunction "2_2") (pintype "unspecified"))
    )
    (net (code "67") (name "Net-(R8-Pad1)") (class "Default")
      (node (ref "R8") (pin "1") (pinfunction "1_1") (pintype "unspecified"))
      (node (ref "SW1") (pin "2") (pinfunction "2_2") (pintype "unspecified"))
    )
    (net (code "68") (name "Net-(R11-Pad2)") (class "Default")
      (node (ref "R11") (pin "2") (pinfunction "2_2") (pintype "unspecified"))
      (node (ref "R14") (pin "1") (pinfunction "1_1") (pintype "unspecified"))
    )
    (net (code "69") (name "Net-(R13-Pad1)") (class "Default")
      (node (ref "R13") (pin "1") (pinfunction "1_1") (pintype "unspecified"))
      (node (ref "R15") (pin "2") (pinfunction "2_2") (pintype "unspecified"))
    )
    (net (code "70") (name "Net-(U4-PDR_ON)") (class "Default")
      (node (ref "R26") (pin "1") (pinfunction "1_1") (pintype "unspecified"))
      (node (ref "R28") (pin "1") (pinfunction "1_1") (pintype "unspecified"))
      (node (ref "U4") (pin "143") (pinfunction "PDR_ON_143") (pintype "unspecified"))
    )
    (net (code "71") (name "Net-(U4-PH0-OSC_IN)") (class "Default")
      (node (ref "C10") (pin "1") (pinfunction "1_1") (pintype "unspecified"))
      (node (ref "R20") (pin "1") (pinfunction "1_1") (pintype "unspecified"))
      (node (ref "U4") (pin "23") (pinfunction "PH0-OSC_IN_23") (pintype "unspecified"))
      (node (ref "Y2") (pin "1") (pinfunction "1_1") (pintype "unspecified"))
    )
    (net (code "72") (name "Net-(U4-PH1-OSC_OUT)") (class "Default")
      (node (ref "C9") (pin "1") (pinfunction "1_1") (pintype "unspecified"))
      (node (ref "R20") (pin "2") (pinfunction "2_2") (pintype "unspecified"))
      (node (ref "U4") (pin "24") (pinfunction "PH1-OSC_OUT_24") (pintype "unspecified"))
      (node (ref "Y2") (pin "2") (pinfunction "2_2") (pintype "unspecified"))
    )
    (net (code "73") (name "Net-(U4-Vcap_1)") (class "Default")
      (node (ref "C11") (pin "1") (pinfunction "1_1") (pintype "unspecified"))
      (node (ref "U4") (pin "71") (pinfunction "Vcap_1_71") (pintype "unspecified"))
    )
    (net (code "74") (name "Net-(U4-Vcap_2)") (class "Default")
      (node (ref "C12") (pin "1") (pinfunction "1_1") (pintype "unspecified"))
      (node (ref "U4") (pin "106") (pinfunction "Vcap_2_106") (pintype "unspecified"))
    )
    (net (code "75") (name "Net-(U10-DATA)") (class "Default")
      (node (ref "U10") (pin "3") (pinfunction "DATA_3") (pintype "unspecified"))
      (node (ref "U18") (pin "2") (pinfunction "D2_2") (pintype "unspecified"))
    )
    (net (code "76") (name "Net-(U11-DATA)") (class "Default")
      (node (ref "U11") (pin "3") (pinfunction "DATA_3") (pintype "unspecified"))
      (node (ref "U18") (pin "1") (pinfunction "D1_1") (pintype "unspecified"))
    )
    (net (code "77") (name "Net-(U12-DATA)") (class "Default")
      (node (ref "U12") (pin "3") (pinfunction "DATA_3") (pintype "unspecified"))
      (node (ref "U18") (pin "3") (pinfunction "D3_3") (pintype "unspecified"))
    )
    (net (code "78") (name "Net-(U13-DATA)") (class "Default")
      (node (ref "U13") (pin "3") (pinfunction "DATA_3") (pintype "unspecified"))
      (node (ref "U18") (pin "4") (pinfunction "D4_4") (pintype "unspecified"))
    )
    (net (code "79") (name "Net-(U19-D)") (class "Default")
      (node (ref "U19") (pin "4") (pinfunction "D_4") (pintype "unspecified"))
      (node (ref "U21") (pin "3") (pinfunction "C_3") (pintype "unspecified"))
    )
    (net (code "80") (name "Net-(U20-D)") (class "Default")
      (node (ref "U20") (pin "4") (pinfunction "D_4") (pintype "unspecified"))
      (node (ref "U22") (pin "3") (pinfunction "C_3") (pintype "unspecified"))
    )
    (net (code "81") (name "Net-(U23-RS232.RXD)") (class "Default")
      (node (ref "U23") (pin "8") (pinfunction "RS232.RXD_8") (pintype "unspecified"))
      (node (ref "U24") (pin "4") (pinfunction "RX_4") (pintype "unspecified"))
    )
    (net (code "82") (name "Net-(U23-RS232.TXD)") (class "Default")
      (node (ref "U23") (pin "7") (pinfunction "RS232.TXD_7") (pintype "unspecified"))
      (node (ref "U24") (pin "3") (pinfunction "TX_3") (pintype "unspecified"))
    )
    (net (code "83") (name "Net-(U24-5V)") (class "Default")
      (node (ref "U23") (pin "5") (pinfunction "VCC_5") (pintype "unspecified"))
      (node (ref "U24") (pin "1") (pinfunction "5V_1") (pintype "unspecified"))
    )
    (net (code "84") (name "Net-(U24-GND)") (class "Default")
      (node (ref "U23") (pin "6") (pinfunction "GND_6") (pintype "unspecified"))
      (node (ref "U24") (pin "2") (pinfunction "GND_2") (pintype "unspecified"))
    )
    (net (code "85") (name "Net-(U25-UD+)") (class "Default")
      (node (ref "U25") (pin "1") (pinfunction "UD+_1") (pintype "unspecified"))
      (node (ref "USB1") (pin "B5") (pinfunction "D+_B5") (pintype "unspecified"))
    )
    (net (code "86") (name "Net-(U25-UD-)") (class "Default")
      (node (ref "U25") (pin "2") (pinfunction "UD-_2") (pintype "unspecified"))
      (node (ref "USB1") (pin "A5") (pinfunction "D-_A5") (pintype "unspecified"))
    )
    (net (code "87") (name "Net-(U25-VCC)") (class "Default")
      (node (ref "D1") (pin "1") (pinfunction "1_1") (pintype "unspecified"))
      (node (ref "U25") (pin "5") (pinfunction "VCC_5") (pintype "unspecified"))
    )
    (net (code "88") (name "PA0{slash}WK_UP") (class "Default")
      (node (ref "J2") (pin "23") (pinfunction "23_23") (pintype "unspecified"))
      (node (ref "U4") (pin "34") (pinfunction "PA0-WKUP/U2_CTS/U4_TX/ETH_MII_CRS/TIM2_CH1_ETR/TIM5_CH1/TIM8_ETR/ADC123_IN0_34") (pintype "unspecified"))
    )
    (net (code "89") (name "PA1") (class "Default")
      (node (ref "J2") (pin "26") (pinfunction "26_26") (pintype "unspecified"))
      (node (ref "U4") (pin "35") (pinfunction "PA1/U2_RTS/U4_RX/ETH_RMII_REF_CLK/ETH_MII_RX_CLK/TIM2_CH2/TIM5_CH2/ADC123_IN1_35") (pintype "unspecified"))
    )
    (net (code "90") (name "PA2") (class "Default")
      (node (ref "J2") (pin "25") (pinfunction "25_25") (pintype "unspecified"))
      (node (ref "U4") (pin "36") (pinfunction "PA2/U2_TX/TIM2_CH3/TIM5_CH3/TIM9_CH1/ETH_MDIO/ADC123_IN2_36") (pintype "unspecified"))
    )
    (net (code "91") (name "PA3") (class "Default")
      (node (ref "J2") (pin "28") (pinfunction "28_28") (pintype "unspecified"))
      (node (ref "U4") (pin "37") (pinfunction "PA3/U2_RX/TIM2_CH4/TIM5_CH4/TIM9_CH2/OTG_HS_ULPI_D0/ETH_MII_COL/ADC123_IN3_37") (pintype "unspecified"))
    )
    (net (code "92") (name "PA4") (class "Default")
      (node (ref "J2") (pin "27") (pinfunction "27_27") (pintype "unspecified"))
      (node (ref "U4") (pin "40") (pinfunction "PA4/SPI1_NSS/U2_CK/DCMI_HSYNC/OTG_HS_SOF/I2S3_WS/DAC1_OUT/ADC12_IN4_40") (pintype "unspecified"))
    )
    (net (code "93") (name "PA5") (class "Default")
      (node (ref "J2") (pin "30") (pinfunction "30_30") (pintype "unspecified"))
      (node (ref "U4") (pin "41") (pinfunction "PA5/SPI1_SCK/OTG_HS_ULPI_CK/TIM2_CH1_ETR/TIM8_CH1N/DAC2_OUT/ADC12_IN5_41") (pintype "unspecified"))
    )
    (net (code "94") (name "PA6") (class "Default")
      (node (ref "J2") (pin "29") (pinfunction "29_29") (pintype "unspecified"))
      (node (ref "U4") (pin "42") (pinfunction "PA6/SPI1_MISO/TIM1_BKIN/TIM3_CH1/TIM8_BKIN/TIM13_CH1/DCMI_PIXCLK/ADC12_IN6_42") (pintype "unspecified"))
    )
    (net (code "95") (name "PA7") (class "Default")
      (node (ref "J2") (pin "32") (pinfunction "32_32") (pintype "unspecified"))
      (node (ref "U4") (pin "43") (pinfunction "PA7/SPI1_MOSI/TIM1_CH1N/TIM3_CH2/TIM8_CH1N/TIM14_CH1/ETH_MII_RX_DV/ETH_RMII_CRS_DV/ADC12_IN7_43") (pintype "unspecified"))
    )
    (net (code "96") (name "PA8") (class "Default")
      (node (ref "J3") (pin "33") (pinfunction "33_33") (pintype "unspecified"))
      (node (ref "U4") (pin "100") (pinfunction "PA8/TIM1_CH1/U1_CK/I2C3_SCL/MCO1/OTG_FS_SOF_100") (pintype "unspecified"))
    )
    (net (code "97") (name "PA9{slash}TXD1") (class "Default")
      (node (ref "J3") (pin "32") (pinfunction "32_32") (pintype "unspecified"))
      (node (ref "U4") (pin "101") (pinfunction "PA9/TIM1_CH2/U1_TX/I2C3_SMBA/OTG_FS_VBUS/DCMI_D0_101") (pintype "unspecified"))
    )
    (net (code "98") (name "PA10{slash}RXD1") (class "Default")
      (node (ref "J3") (pin "31") (pinfunction "31_31") (pintype "unspecified"))
      (node (ref "U4") (pin "102") (pinfunction "PA10/TIM1_CH3/U1_RX/OTG_FS_ID/DCMI_D1_102") (pintype "unspecified"))
    )
    (net (code "99") (name "PA11{slash}USB_DM") (class "Default")
      (node (ref "J3") (pin "30") (pinfunction "30_30") (pintype "unspecified"))
      (node (ref "U4") (pin "103") (pinfunction "PA11/TIM1_CH4/U1_CTS/CAN1_RX/OTG_FS_DM_103") (pintype "unspecified"))
    )
    (net (code "100") (name "PA12{slash}USB_DP") (class "Default")
      (node (ref "J3") (pin "29") (pinfunction "29_29") (pintype "unspecified"))
      (node (ref "U4") (pin "104") (pinfunction "PA12/TIM1_ETR/U1_RTS/CAN1_TX/OTG_FS_DP_104") (pintype "unspecified"))
    )
    (net (code "101") (name "PA13{slash}TMS") (class "Default")
      (node (ref "J1") (pin "7") (pinfunction "TMS_7") (pintype "unspecified"))
      (node (ref "J3") (pin "28") (pinfunction "28_28") (pintype "unspecified"))
      (node (ref "R18") (pin "2") (pinfunction "2_2") (pintype "unspecified"))
      (node (ref "U4") (pin "105") (pinfunction "PA13/JTMS_SWDIO_105") (pintype "unspecified"))
    )
    (net (code "102") (name "PA14{slash}TCK") (class "Default")
      (node (ref "J1") (pin "9") (pinfunction "TCK_9") (pintype "unspecified"))
      (node (ref "J3") (pin "27") (pinfunction "27_27") (pintype "unspecified"))
      (node (ref "R16") (pin "2") (pinfunction "2_2") (pintype "unspecified"))
      (node (ref "U4") (pin "109") (pinfunction "PA14/JTCK_SWCLK_109") (pintype "unspecified"))
    )
    (net (code "103") (name "PA15{slash}TDI") (class "Default")
      (node (ref "J1") (pin "5") (pinfunction "TDI_5") (pintype "unspecified"))
      (node (ref "J3") (pin "26") (pinfunction "26_26") (pintype "unspecified"))
      (node (ref "R19") (pin "2") (pinfunction "2_2") (pintype "unspecified"))
      (node (ref "U4") (pin "110") (pinfunction "PA15/JTDI/SPI1_NSS/SPI3_NSS/TIM2_CH1_ETR/I2S3_WS_110") (pintype "unspecified"))
    )
    (net (code "104") (name "PB0") (class "Default")
      (node (ref "J2") (pin "33") (pinfunction "33_33") (pintype "unspecified"))
      (node (ref "U4") (pin "46") (pinfunction "PB0/TIM1_CH2N/TIM3_CH3/TIM8_CH2N/OTG_HS_ULPI_D1/ETH_MII_RXD2/ADC12_IN8_46") (pintype "unspecified"))
    )
    (net (code "105") (name "PB1") (class "Default")
      (node (ref "J2") (pin "36") (pinfunction "36_36") (pintype "unspecified"))
      (node (ref "U4") (pin "47") (pinfunction "PB1/TIM1_CH3N/TIM3_CH4/TIM8_CH3N/OTG_HS_INTN/ETH_MII_RXD3/ADC12_IN9_47") (pintype "unspecified"))
    )
    (net (code "106") (name "PB2{slash}BOOT1") (class "Default")
      (node (ref "J2") (pin "35") (pinfunction "35_35") (pintype "unspecified"))
      (node (ref "J2") (pin "58") (pinfunction "58_58") (pintype "unspecified"))
      (node (ref "R12") (pin "1") (pinfunction "1_1") (pintype "unspecified"))
      (node (ref "U4") (pin "48") (pinfunction "PB2/BOOT1_48") (pintype "unspecified"))
    )
    (net (code "107") (name "PB3{slash}TDO") (class "Default")
      (node (ref "J1") (pin "13") (pinfunction "TDO_13") (pintype "unspecified"))
      (node (ref "J3") (pin "7") (pinfunction "7_7") (pintype "unspecified"))
      (node (ref "R17") (pin "2") (pinfunction "2_2") (pintype "unspecified"))
      (node (ref "U4") (pin "133") (pinfunction "PB3/JTDO/TRACESWO/TIM2_CH2/SPI1_SCK/SPI3_SCK/I2S3_CK_133") (pintype "unspecified"))
    )
    (net (code "108") (name "PB4{slash}TRST") (class "Default")
      (node (ref "J1") (pin "3") (pinfunction "nTRST_3") (pintype "unspecified"))
      (node (ref "J3") (pin "6") (pinfunction "6_6") (pintype "unspecified"))
      (node (ref "R23") (pin "2") (pinfunction "2_2") (pintype "unspecified"))
      (node (ref "U4") (pin "134") (pinfunction "PB4/JNTRST/TIM3_CH1/SPI1_MISO/SPI3_MISO/I2S3ext_SD_134") (pintype "unspecified"))
    )
    (net (code "109") (name "PB5") (class "Default")
      (node (ref "J3") (pin "5") (pinfunction "5_5") (pintype "unspecified"))
      (node (ref "U4") (pin "135") (pinfunction "PB5/TIM3_CH2/SPI1_MOSI/SPI3_MOSI/CAN2_RX/I2C1_SMBA/OTG_HS_ULPI_D7/ETH_PPS_OUT/DCMI_D10/I2S3_SD_135") (pintype "unspecified"))
    )
    (net (code "110") (name "PB6") (class "Default")
      (node (ref "J3") (pin "4") (pinfunction "4_4") (pintype "unspecified"))
      (node (ref "U4") (pin "136") (pinfunction "PB6/TIM4_CH1/U1_TX/CAN2_TX/I2C1_SCL/DCMI_D5_136") (pintype "unspecified"))
    )
    (net (code "111") (name "PB7") (class "Default")
      (node (ref "J3") (pin "3") (pinfunction "3_3") (pintype "unspecified"))
      (node (ref "U4") (pin "137") (pinfunction "PB7/TIM4_CH2/U1_RX/FSMC_NL/I2C1_SDA/DCMI_VSYNC_137") (pintype "unspecified"))
    )
    (net (code "112") (name "PB8") (class "Default")
      (node (ref "J3") (pin "2") (pinfunction "2_2") (pintype "unspecified"))
      (node (ref "U4") (pin "139") (pinfunction "PB8/TIM4_CH3/TIM10_CH1/CAN1_RX/SDIO_D4/ETH_MII_TXD3/I2C1_SCL/DCMI_D6_139") (pintype "unspecified"))
    )
    (net (code "113") (name "PB9") (class "Default")
      (node (ref "J3") (pin "1") (pinfunction "1_1") (pintype "unspecified"))
      (node (ref "U4") (pin "140") (pinfunction "PB9/TIM4_CH4/TIM11_CH1/CAN1_TX/SDIO_D5/SPI2_NSS/I2C1_SDA/DCMI_D7/I2S2_WS_140") (pintype "unspecified"))
    )
    (net (code "114") (name "PB10") (class "Default")
      (node (ref "J2") (pin "54") (pinfunction "54_54") (pintype "unspecified"))
      (node (ref "U4") (pin "69") (pinfunction "PB10/SPI2_SCK/TIM2_CH3/U3_TX/I2C2_SCL/OTG_HS_ULPI_D3/I2S2_CK_69") (pintype "unspecified"))
    )
    (net (code "115") (name "PB11") (class "Default")
      (node (ref "J2") (pin "53") (pinfunction "53_53") (pintype "unspecified"))
      (node (ref "U4") (pin "70") (pinfunction "PB11/TIM2_CH4/U3_RX/I2C2_SDA/HS_ULPI_D4/ETH_MII_TX_EN/ETH_RMII_TX_EN_70") (pintype "unspecified"))
    )
    (net (code "116") (name "PB12") (class "Default")
      (node (ref "J3") (pin "56") (pinfunction "56_56") (pintype "unspecified"))
      (node (ref "U4") (pin "73") (pinfunction "PB12/SPI2_NSS/TIM1_BKIN/U3_CK/CAN2_RX/I2C2_SMBA/OTG_HS_ULPI_D5/OTG_HS_ID/ETH_MII_TXD0/ETH_RMII_TXD0/I2S2_WS_73") (pintype "unspecified"))
    )
    (net (code "117") (name "PB13") (class "Default")
      (node (ref "J3") (pin "55") (pinfunction "55_55") (pintype "unspecified"))
      (node (ref "U4") (pin "74") (pinfunction "PB13/SPI2_SCK/TIM1_CH1N/U3_CTS/CAN2_TX/OTG_HS_ULPI_D6/OTG_HS_VBUS/ETH_MII_TXD1/ETH_RMII_TXD1/I2S2_CK_74") (pintype "unspecified"))
    )
    (net (code "118") (name "PC0") (class "Default")
      (node (ref "J2") (pin "19") (pinfunction "19_19") (pintype "unspecified"))
      (node (ref "U4") (pin "26") (pinfunction "PC0/OTG_HS_ULPI_STP/ADC123_IN10_26") (pintype "unspecified"))
    )
    (net (code "119") (name "PC1") (class "Default")
      (node (ref "J2") (pin "22") (pinfunction "22_22") (pintype "unspecified"))
      (node (ref "U4") (pin "27") (pinfunction "PC1/ETH_MDC/ADC123_IN11_27") (pintype "unspecified"))
    )
    (net (code "120") (name "PC2") (class "Default")
      (node (ref "J2") (pin "21") (pinfunction "21_21") (pintype "unspecified"))
      (node (ref "U4") (pin "28") (pinfunction "PC2/SPI2_MISO/OTG_HS_ULPI_DIR/ETH_MII_TXD2/I2S2ext_SD/ADC123_IN12_28") (pintype "unspecified"))
    )
    (net (code "121") (name "PC3") (class "Default")
      (node (ref "J2") (pin "24") (pinfunction "24_24") (pintype "unspecified"))
      (node (ref "U4") (pin "29") (pinfunction "PC3/SPI2_MOSI/OTG_HS_ULPI_NXT/ETH_MII_TX_CLK/I2S2_SD/ADC123_IN13_29") (pintype "unspecified"))
    )
    (net (code "122") (name "PC4") (class "Default")
      (node (ref "J2") (pin "31") (pinfunction "31_31") (pintype "unspecified"))
      (node (ref "U4") (pin "44") (pinfunction "PC4/ETH_MII_RXD0/ETH_RMII_RXD0/ADC12_IN14_44") (pintype "unspecified"))
    )
    (net (code "123") (name "PC5") (class "Default")
      (node (ref "J2") (pin "34") (pinfunction "34_34") (pintype "unspecified"))
      (node (ref "U4") (pin "45") (pinfunction "PC5/ETH_MII_RXD1/ETH_RMII_RXD1/ADC12_IN15_45") (pintype "unspecified"))
    )
    (net (code "124") (name "PC6") (class "Default")
      (node (ref "J3") (pin "37") (pinfunction "37_37") (pintype "unspecified"))
      (node (ref "U4") (pin "96") (pinfunction "PC6/TIM3_CH1/TIM8_CH1/U6_TX/SDIO_D6/DCMI_D0/I2S2_MCK_96") (pintype "unspecified"))
    )
    (net (code "125") (name "PC7") (class "Default")
      (node (ref "J3") (pin "36") (pinfunction "36_36") (pintype "unspecified"))
      (node (ref "U4") (pin "97") (pinfunction "PC7/TIM3_CH2/TIM8_CH2/U6_RX/SDIO_D7/DCMI_D1/I2S3_MCK_97") (pintype "unspecified"))
    )
    (net (code "126") (name "PC8") (class "Default")
      (node (ref "J3") (pin "35") (pinfunction "35_35") (pintype "unspecified"))
      (node (ref "U4") (pin "98") (pinfunction "PC8/TIM3_CH3/TIM8_CH3/U6_CK/SDIO_D0/DCMI_D2_98") (pintype "unspecified"))
    )
    (net (code "127") (name "PC9") (class "Default")
      (node (ref "J3") (pin "34") (pinfunction "34_34") (pintype "unspecified"))
      (node (ref "U4") (pin "99") (pinfunction "PC9/TIM3_CH4/TIM8_CH4/I2C3_SDA/SDIO_D1/DCMI_D3/MCO2/I2S_CKIN_99") (pintype "unspecified"))
    )
    (net (code "128") (name "PC10") (class "Default")
      (node (ref "J3") (pin "25") (pinfunction "25_25") (pintype "unspecified"))
      (node (ref "U4") (pin "111") (pinfunction "PC10/SPI3_SCK/U3_TX/U4_TX/SDIO_D2/DCMI_D8/I2S3_CK_111") (pintype "unspecified"))
    )
    (net (code "129") (name "PC11") (class "Default")
      (node (ref "J3") (pin "24") (pinfunction "24_24") (pintype "unspecified"))
      (node (ref "U4") (pin "112") (pinfunction "PC11/SPI3_MISO/U3_RX/U4_RX/SDIO_D3/DCMI_D4/I2S3ext_SD_112") (pintype "unspecified"))
    )
    (net (code "130") (name "PC12") (class "Default")
      (node (ref "J3") (pin "23") (pinfunction "23_23") (pintype "unspecified"))
      (node (ref "U4") (pin "113") (pinfunction "PC12/SPI3_MOSI/U3_CK/U5_TX/SDIO_CK/DCMI_D9/I2S3_SD_113") (pintype "unspecified"))
    )
    (net (code "131") (name "PC13") (class "Default")
      (node (ref "J2") (pin "7") (pinfunction "7_7") (pintype "unspecified"))
      (node (ref "U4") (pin "7") (pinfunction "PC13/RTC_AF1_7") (pintype "unspecified"))
    )
    (net (code "132") (name "PC14") (class "Default")
      (node (ref "C7") (pin "2") (pinfunction "2_2") (pintype "unspecified"))
      (node (ref "U4") (pin "8") (pinfunction "PC14-OSC32_IN_8") (pintype "unspecified"))
      (node (ref "Y1") (pin "2") (pinfunction "2_2") (pintype "unspecified"))
    )
    (net (code "133") (name "PC15") (class "Default")
      (node (ref "C8") (pin "2") (pinfunction "2_2") (pintype "unspecified"))
      (node (ref "U4") (pin "9") (pinfunction "PC15-OSC32_OUT_9") (pintype "unspecified"))
      (node (ref "Y1") (pin "1") (pinfunction "1_1") (pintype "unspecified"))
    )
    (net (code "134") (name "PD2") (class "Default")
      (node (ref "J3") (pin "20") (pinfunction "20_20") (pintype "unspecified"))
      (node (ref "U4") (pin "116") (pinfunction "PD2/TIM3_ETR/U5_RX/SDIO_CMD/DCMI_D11_116") (pintype "unspecified"))
    )
    (net (code "135") (name "PD3") (class "Default")
      (node (ref "J3") (pin "19") (pinfunction "19_19") (pintype "unspecified"))
      (node (ref "U4") (pin "117") (pinfunction "PD3/FSMC_CLK/U2_CTS_117") (pintype "unspecified"))
    )
    (net (code "136") (name "PD6") (class "Default")
      (node (ref "J3") (pin "16") (pinfunction "16_16") (pintype "unspecified"))
      (node (ref "U4") (pin "122") (pinfunction "PD6/FSMC_NWAIT/U2_RX_122") (pintype "unspecified"))
    )
    (net (code "137") (name "PD7") (class "Default")
      (node (ref "J3") (pin "15") (pinfunction "15_15") (pintype "unspecified"))
      (node (ref "U4") (pin "123") (pinfunction "PD7/FSMC_NE1/FSMC_NCE2/U2_CK_123") (pintype "unspecified"))
    )
    (net (code "138") (name "PE2") (class "Default")
      (node (ref "J2") (pin "4") (pinfunction "4_4") (pintype "unspecified"))
      (node (ref "U4") (pin "1") (pinfunction "PE2/TRACECLK/FSMC_A23/ETH_MII_TXD3_1") (pintype "unspecified"))
    )
    (net (code "139") (name "PF6") (class "Default")
      (node (ref "J2") (pin "16") (pinfunction "16_16") (pintype "unspecified"))
      (node (ref "U4") (pin "18") (pinfunction "PF6/TIM10_CH1/FSMC_NIORD/ADC3_IN4_18") (pintype "unspecified"))
    )
    (net (code "140") (name "PF7") (class "Default")
      (node (ref "J2") (pin "15") (pinfunction "15_15") (pintype "unspecified"))
      (node (ref "U4") (pin "19") (pinfunction "PF7/TIM11_CH1/FSMC_NREG/ADC3_IN5_19") (pintype "unspecified"))
    )
    (net (code "141") (name "PF8") (class "Default")
      (node (ref "J2") (pin "18") (pinfunction "18_18") (pintype "unspecified"))
      (node (ref "U4") (pin "20") (pinfunction "PF8/TIM13_CH1/FSMC_NIOWR/ADC3_IN6_20") (pintype "unspecified"))
    )
    (net (code "142") (name "PF11") (class "Default")
      (node (ref "J2") (pin "38") (pinfunction "38_38") (pintype "unspecified"))
      (node (ref "U4") (pin "49") (pinfunction "PF11/DCMI_D12_49") (pintype "unspecified"))
    )
    (net (code "143") (name "PG9") (class "Default")
      (node (ref "J3") (pin "14") (pinfunction "14_14") (pintype "unspecified"))
      (node (ref "U4") (pin "124") (pinfunction "PG9/FSMC_NE2/FSMC_NCE3/U6_RX_124") (pintype "unspecified"))
    )
    (net (code "144") (name "PG11") (class "Default")
      (node (ref "J3") (pin "12") (pinfunction "12_12") (pintype "unspecified"))
      (node (ref "U4") (pin "126") (pinfunction "PG11/FSMC_NCE4_2/ETH_MII_TX_EN/ETH_RMII_TX_EN_126") (pintype "unspecified"))
    )
    (net (code "145") (name "PG13") (class "Default")
      (node (ref "J3") (pin "10") (pinfunction "10_10") (pintype "unspecified"))
      (node (ref "U4") (pin "128") (pinfunction "PG13/FSMC_A24/U6_CTS/ETH_MII_TXD0/ETH_RMII_TXD0_128") (pintype "unspecified"))
    )
    (net (code "146") (name "PG14") (class "Default")
      (node (ref "J3") (pin "9") (pinfunction "9_9") (pintype "unspecified"))
      (node (ref "U4") (pin "129") (pinfunction "PG14/FSMC_A25/U6_TX/ETH_MII_TXD1/ETH_RMII_TXD1_129") (pintype "unspecified"))
    )
    (net (code "147") (name "PG15") (class "Default")
      (node (ref "J3") (pin "8") (pinfunction "8_8") (pintype "unspecified"))
      (node (ref "U4") (pin "132") (pinfunction "PG15/U6_CTS/DCMI_D13_132") (pintype "unspecified"))
    )
    (net (code "148") (name "RST") (class "Default")
      (node (ref "C14") (pin "2") (pinfunction "2_2") (pintype "unspecified"))
      (node (ref "J1") (pin "15") (pinfunction "nSRST_15") (pintype "unspecified"))
      (node (ref "R24") (pin "1") (pinfunction "1_1") (pintype "unspecified"))
      (node (ref "RST") (pin "1") (pinfunction "C1_1") (pintype "unspecified"))
      (node (ref "U4") (pin "25") (pinfunction "NRST_25") (pintype "unspecified"))
    )
    (net (code "149") (name "VBAT") (class "Default")
      (node (ref "U4") (pin "6") (pinfunction "VBAT_6") (pintype "unspecified"))
    )
    (net (code "150") (name "VCC") (class "Default")
      (node (ref "R5") (pin "1") (pinfunction "1_1") (pintype "unspecified"))
      (node (ref "R9") (pin "1") (pinfunction "1_1") (pintype "unspecified"))
      (node (ref "U15") (pin "1") (pinfunction "VIN_1") (pintype "unspecified"))
      (node (ref "U16") (pin "1") (pinfunction "VIN_1") (pintype "unspecified"))
      (node (ref "U17") (pin "1") (pinfunction "VIN_1") (pintype "unspecified"))
      (node (ref "U3") (pin "1") (pinfunction "V+_1") (pintype "unspecified"))
      (node (ref "U5") (pin "1") (pinfunction "V+_1") (pintype "unspecified"))
      (node (ref "U6") (pin "1") (pinfunction "V+_1") (pintype "unspecified"))
      (node (ref "U7") (pin "1") (pinfunction "V+_1") (pintype "unspecified"))
    )
    (net (code "151") (name "VDDA") (class "Default")
      (node (ref "C15") (pin "2") (pinfunction "2_2") (pintype "unspecified"))
      (node (ref "C16") (pin "2") (pinfunction "2_2") (pintype "unspecified"))
      (node (ref "R21") (pin "2") (pinfunction "2_2") (pintype "unspecified"))
      (node (ref "R22") (pin "1") (pinfunction "1_1") (pintype "unspecified"))
      (node (ref "U4") (pin "33") (pinfunction "VDDA_33") (pintype "unspecified"))
    )
    (net (code "152") (name "VREF+") (class "Default")
      (node (ref "C33") (pin "1") (pinfunction "1_1") (pintype "unspecified"))
      (node (ref "J2") (pin "56") (pinfunction "56_56") (pintype "unspecified"))
      (node (ref "R21") (pin "1") (pinfunction "1_1") (pintype "unspecified"))
      (node (ref "U4") (pin "32") (pinfunction "Vref+_32") (pintype "unspecified"))
    )
    (net (code "153") (name "unconnected-(J1-NC-Pad17)") (class "Default")
      (node (ref "J1") (pin "17") (pinfunction "NC_17") (pintype "unspecified"))
    )
    (net (code "154") (name "unconnected-(J1-NC-Pad19)") (class "Default")
      (node (ref "J1") (pin "19") (pinfunction "NC_19") (pintype "unspecified"))
    )
    (net (code "155") (name "unconnected-(J1-RTCK-Pad11)") (class "Default")
      (node (ref "J1") (pin "11") (pinfunction "RTCK_11") (pintype "unspecified"))
    )
    (net (code "156") (name "unconnected-(U1-SCL-Pad3)") (class "Default")
      (node (ref "U1") (pin "3") (pinfunction "SCL_3") (pintype "unspecified"))
    )
    (net (code "157") (name "unconnected-(U1-SDA-Pad4)") (class "Default")
      (node (ref "U1") (pin "4") (pinfunction "SDA_4") (pintype "unspecified"))
    )
    (net (code "158") (name "unconnected-(U2-RX-Pad2)") (class "Default")
      (node (ref "U2") (pin "2") (pinfunction "RX_2") (pintype "unspecified"))
    )
    (net (code "159") (name "unconnected-(U2-TX-Pad3)") (class "Default")
      (node (ref "U2") (pin "3") (pinfunction "TX_3") (pintype "unspecified"))
    )
    (net (code "160") (name "unconnected-(U3-Com-Pad3)") (class "Default")
      (node (ref "U3") (pin "3") (pinfunction "Com_3") (pintype "unspecified+no_connect"))
    )
    (net (code "161") (name "unconnected-(U3-Dir-Pad6)") (class "Default")
      (node (ref "U3") (pin "6") (pinfunction "Dir_6") (pintype "unspecified"))
    )
    (net (code "162") (name "unconnected-(U3-En-Pad4)") (class "Default")
      (node (ref "U3") (pin "4") (pinfunction "En_4") (pintype "unspecified"))
    )
    (net (code "163") (name "unconnected-(U3-Stp-Pad5)") (class "Default")
      (node (ref "U3") (pin "5") (pinfunction "Stp_5") (pintype "unspecified"))
    )
    (net (code "164") (name "unconnected-(U5-Com-Pad3)") (class "Default")
      (node (ref "U5") (pin "3") (pinfunction "Com_3") (pintype "unspecified+no_connect"))
    )
    (net (code "165") (name "unconnected-(U5-Dir-Pad6)") (class "Default")
      (node (ref "U5") (pin "6") (pinfunction "Dir_6") (pintype "unspecified"))
    )
    (net (code "166") (name "unconnected-(U5-En-Pad4)") (class "Default")
      (node (ref "U5") (pin "4") (pinfunction "En_4") (pintype "unspecified"))
    )
    (net (code "167") (name "unconnected-(U5-Stp-Pad5)") (class "Default")
      (node (ref "U5") (pin "5") (pinfunction "Stp_5") (pintype "unspecified"))
    )
    (net (code "168") (name "unconnected-(U6-Com-Pad3)") (class "Default")
      (node (ref "U6") (pin "3") (pinfunction "Com_3") (pintype "unspecified+no_connect"))
    )
    (net (code "169") (name "unconnected-(U6-Dir-Pad6)") (class "Default")
      (node (ref "U6") (pin "6") (pinfunction "Dir_6") (pintype "unspecified"))
    )
    (net (code "170") (name "unconnected-(U6-En-Pad4)") (class "Default")
      (node (ref "U6") (pin "4") (pinfunction "En_4") (pintype "unspecified"))
    )
    (net (code "171") (name "unconnected-(U6-Stp-Pad5)") (class "Default")
      (node (ref "U6") (pin "5") (pinfunction "Stp_5") (pintype "unspecified"))
    )
    (net (code "172") (name "unconnected-(U7-Com-Pad3)") (class "Default")
      (node (ref "U7") (pin "3") (pinfunction "Com_3") (pintype "unspecified+no_connect"))
    )
    (net (code "173") (name "unconnected-(U7-Dir-Pad6)") (class "Default")
      (node (ref "U7") (pin "6") (pinfunction "Dir_6") (pintype "unspecified"))
    )
    (net (code "174") (name "unconnected-(U7-En-Pad4)") (class "Default")
      (node (ref "U7") (pin "4") (pinfunction "En_4") (pintype "unspecified"))
    )
    (net (code "175") (name "unconnected-(U7-Stp-Pad5)") (class "Default")
      (node (ref "U7") (pin "5") (pinfunction "Stp_5") (pintype "unspecified"))
    )
    (net (code "176") (name "unconnected-(U8-DATA-Pad3)") (class "Default")
      (node (ref "U8") (pin "3") (pinfunction "DATA_3") (pintype "unspecified"))
    )
    (net (code "177") (name "unconnected-(U9-DATA-Pad3)") (class "Default")
      (node (ref "U9") (pin "3") (pinfunction "DATA_3") (pintype "unspecified"))
    )
    (net (code "178") (name "unconnected-(U14-3V3_OUT-Pad8)") (class "Default")
      (node (ref "U14") (pin "8") (pinfunction "3V3_OUT_8") (pintype "unspecified+no_connect"))
    )
    (net (code "179") (name "unconnected-(U14-BOOT0-Pad15)") (class "Default")
      (node (ref "U14") (pin "15") (pinfunction "BOOT0_15") (pintype "unspecified+no_connect"))
    )
    (net (code "180") (name "unconnected-(U14-FRAMESYNC-Pad14)") (class "Default")
      (node (ref "U14") (pin "14") (pinfunction "FRAMESYNC_14") (pintype "unspecified+no_connect"))
    )
    (net (code "181") (name "unconnected-(U14-P0{slash}UART1_RX-Pad1)") (class "Default")
      (node (ref "U14") (pin "1") (pinfunction "P0/UART1_RX_1") (pintype "unspecified+no_connect"))
    )
    (net (code "182") (name "unconnected-(U14-P1{slash}UART1_TX-Pad2)") (class "Default")
      (node (ref "U14") (pin "2") (pinfunction "P1/UART1_TX_2") (pintype "unspecified+no_connect"))
    )
    (net (code "183") (name "unconnected-(U14-P2{slash}CAN2_TX-Pad3)") (class "Default")
      (node (ref "U14") (pin "3") (pinfunction "P2/CAN2_TX_3") (pintype "unspecified+no_connect"))
    )
    (net (code "184") (name "unconnected-(U14-P3{slash}CAN2_RX-Pad4)") (class "Default")
      (node (ref "U14") (pin "4") (pinfunction "P3/CAN2_RX_4") (pintype "unspecified+no_connect"))
    )
    (net (code "185") (name "unconnected-(U14-P4{slash}UART3_TX-Pad5)") (class "Default")
      (node (ref "U14") (pin "5") (pinfunction "P4/UART3_TX_5") (pintype "unspecified"))
    )
    (net (code "186") (name "unconnected-(U14-P5{slash}UART3_RX-Pad6)") (class "Default")
      (node (ref "U14") (pin "6") (pinfunction "P5/UART3_RX_6") (pintype "unspecified"))
    )
    (net (code "187") (name "unconnected-(U14-P6-Pad7)") (class "Default")
      (node (ref "U14") (pin "7") (pinfunction "P6_7") (pintype "unspecified+no_connect"))
    )
    (net (code "188") (name "unconnected-(U14-P7-Pad11)") (class "Default")
      (node (ref "U14") (pin "11") (pinfunction "P7_11") (pintype "unspecified+no_connect"))
    )
    (net (code "189") (name "unconnected-(U14-P8-Pad12)") (class "Default")
      (node (ref "U14") (pin "12") (pinfunction "P8_12") (pintype "unspecified+no_connect"))
    )
    (net (code "190") (name "unconnected-(U14-P9-Pad13)") (class "Default")
      (node (ref "U14") (pin "13") (pinfunction "P9_13") (pintype "unspecified+no_connect"))
    )
    (net (code "191") (name "unconnected-(U14-Reset-Pad16)") (class "Default")
      (node (ref "U14") (pin "16") (pinfunction "Reset_16") (pintype "unspecified+no_connect"))
    )
    (net (code "192") (name "unconnected-(U18-3V3-Pad21)") (class "Default")
      (node (ref "U18") (pin "21") (pinfunction "3V3_21") (pintype "unspecified+no_connect"))
    )
    (net (code "193") (name "unconnected-(U18-D5-Pad5)") (class "Default")
      (node (ref "U18") (pin "5") (pinfunction "D5_5") (pintype "unspecified+no_connect"))
    )
    (net (code "194") (name "unconnected-(U18-D6-Pad6)") (class "Default")
      (node (ref "U18") (pin "6") (pinfunction "D6_6") (pintype "unspecified+no_connect"))
    )
    (net (code "195") (name "unconnected-(U18-D7-Pad7)") (class "Default")
      (node (ref "U18") (pin "7") (pinfunction "D7_7") (pintype "unspecified+no_connect"))
    )
    (net (code "196") (name "unconnected-(U18-D8-Pad8)") (class "Default")
      (node (ref "U18") (pin "8") (pinfunction "D8_8") (pintype "unspecified+no_connect"))
    )
    (net (code "197") (name "unconnected-(U18-D9-Pad9)") (class "Default")
      (node (ref "U18") (pin "9") (pinfunction "D9_9") (pintype "unspecified+no_connect"))
    )
    (net (code "198") (name "unconnected-(U18-D10-Pad10)") (class "Default")
      (node (ref "U18") (pin "10") (pinfunction "D10_10") (pintype "unspecified+no_connect"))
    )
    (net (code "199") (name "unconnected-(U18-D11-Pad11)") (class "Default")
      (node (ref "U18") (pin "11") (pinfunction "D11_11") (pintype "unspecified+no_connect"))
    )
    (net (code "200") (name "unconnected-(U18-D12-Pad12)") (class "Default")
      (node (ref "U18") (pin "12") (pinfunction "D12_12") (pintype "unspecified+no_connect"))
    )
    (net (code "201") (name "unconnected-(U18-D13-Pad13)") (class "Default")
      (node (ref "U18") (pin "13") (pinfunction "D13_13") (pintype "unspecified+no_connect"))
    )
    (net (code "202") (name "unconnected-(U18-D14-Pad14)") (class "Default")
      (node (ref "U18") (pin "14") (pinfunction "D14_14") (pintype "unspecified+no_connect"))
    )
    (net (code "203") (name "unconnected-(U18-D15-Pad15)") (class "Default")
      (node (ref "U18") (pin "15") (pinfunction "D15_15") (pintype "unspecified+no_connect"))
    )
    (net (code "204") (name "unconnected-(U18-D16-Pad16)") (class "Default")
      (node (ref "U18") (pin "16") (pinfunction "D16_16") (pintype "unspecified+no_connect"))
    )
    (net (code "205") (name "unconnected-(U18-RX-Pad20)") (class "Default")
      (node (ref "U18") (pin "20") (pinfunction "RX_20") (pintype "unspecified"))
    )
    (net (code "206") (name "unconnected-(U18-TX-Pad19)") (class "Default")
      (node (ref "U18") (pin "19") (pinfunction "TX_19") (pintype "unspecified"))
    )
    (net (code "207") (name "unconnected-(U19-A-Pad1)") (class "Default")
      (node (ref "U19") (pin "1") (pinfunction "A_1") (pintype "unspecified"))
    )
    (net (code "208") (name "unconnected-(U19-B-Pad2)") (class "Default")
      (node (ref "U19") (pin "2") (pinfunction "B_2") (pintype "unspecified"))
    )
    (net (code "209") (name "unconnected-(U20-A-Pad1)") (class "Default")
      (node (ref "U20") (pin "1") (pinfunction "A_1") (pintype "unspecified"))
    )
    (net (code "210") (name "unconnected-(U20-B-Pad2)") (class "Default")
      (node (ref "U20") (pin "2") (pinfunction "B_2") (pintype "unspecified"))
    )
    (net (code "211") (name "unconnected-(U21-A-Pad1)") (class "Default")
      (node (ref "U21") (pin "1") (pinfunction "A_1") (pintype "unspecified"))
    )
    (net (code "212") (name "unconnected-(U21-B-Pad2)") (class "Default")
      (node (ref "U21") (pin "2") (pinfunction "B_2") (pintype "unspecified"))
    )
    (net (code "213") (name "unconnected-(U21-D-Pad4)") (class "Default")
      (node (ref "U21") (pin "4") (pinfunction "D_4") (pintype "unspecified"))
    )
    (net (code "214") (name "unconnected-(U22-A-Pad1)") (class "Default")
      (node (ref "U22") (pin "1") (pinfunction "A_1") (pintype "unspecified"))
    )
    (net (code "215") (name "unconnected-(U22-B-Pad2)") (class "Default")
      (node (ref "U22") (pin "2") (pinfunction "B_2") (pintype "unspecified"))
    )
    (net (code "216") (name "unconnected-(U22-D-Pad4)") (class "Default")
      (node (ref "U22") (pin "4") (pinfunction "D_4") (pintype "unspecified"))
    )
    (net (code "217") (name "unconnected-(U23-TTL.RXD-Pad4)") (class "Default")
      (node (ref "U23") (pin "4") (pinfunction "TTL.RXD_4") (pintype "unspecified"))
    )
    (net (code "218") (name "unconnected-(U23-TTL.TXD-Pad3)") (class "Default")
      (node (ref "U23") (pin "3") (pinfunction "TTL.TXD_3") (pintype "unspecified"))
    )
    (net (code "219") (name "unconnected-(U25-RTS#-Pad4)") (class "Default")
      (node (ref "U25") (pin "4") (pinfunction "RTS#_4") (pintype "unspecified+no_connect"))
    )
    (net (code "220") (name "unconnected-(U25-RXD-Pad7)") (class "Default")
      (node (ref "U25") (pin "7") (pinfunction "RXD_7") (pintype "unspecified"))
    )
    (net (code "221") (name "unconnected-(U25-TXD-Pad6)") (class "Default")
      (node (ref "U25") (pin "6") (pinfunction "TXD_6") (pintype "unspecified"))
    )
    (net (code "222") (name "unconnected-(U25-V3-Pad8)") (class "Default")
      (node (ref "U25") (pin "8") (pinfunction "V3_8") (pintype "unspecified+no_connect"))
    )
    (net (code "223") (name "unconnected-(USB1-VBUS-PadA9)") (class "Default")
      (node (ref "USB1") (pin "A9") (pinfunction "VBUS_A9") (pintype "unspecified+no_connect"))
    )
  )
)
